# MY_beamControl_R.net
KiCad netlist of a schematic drawn in Altium Designer
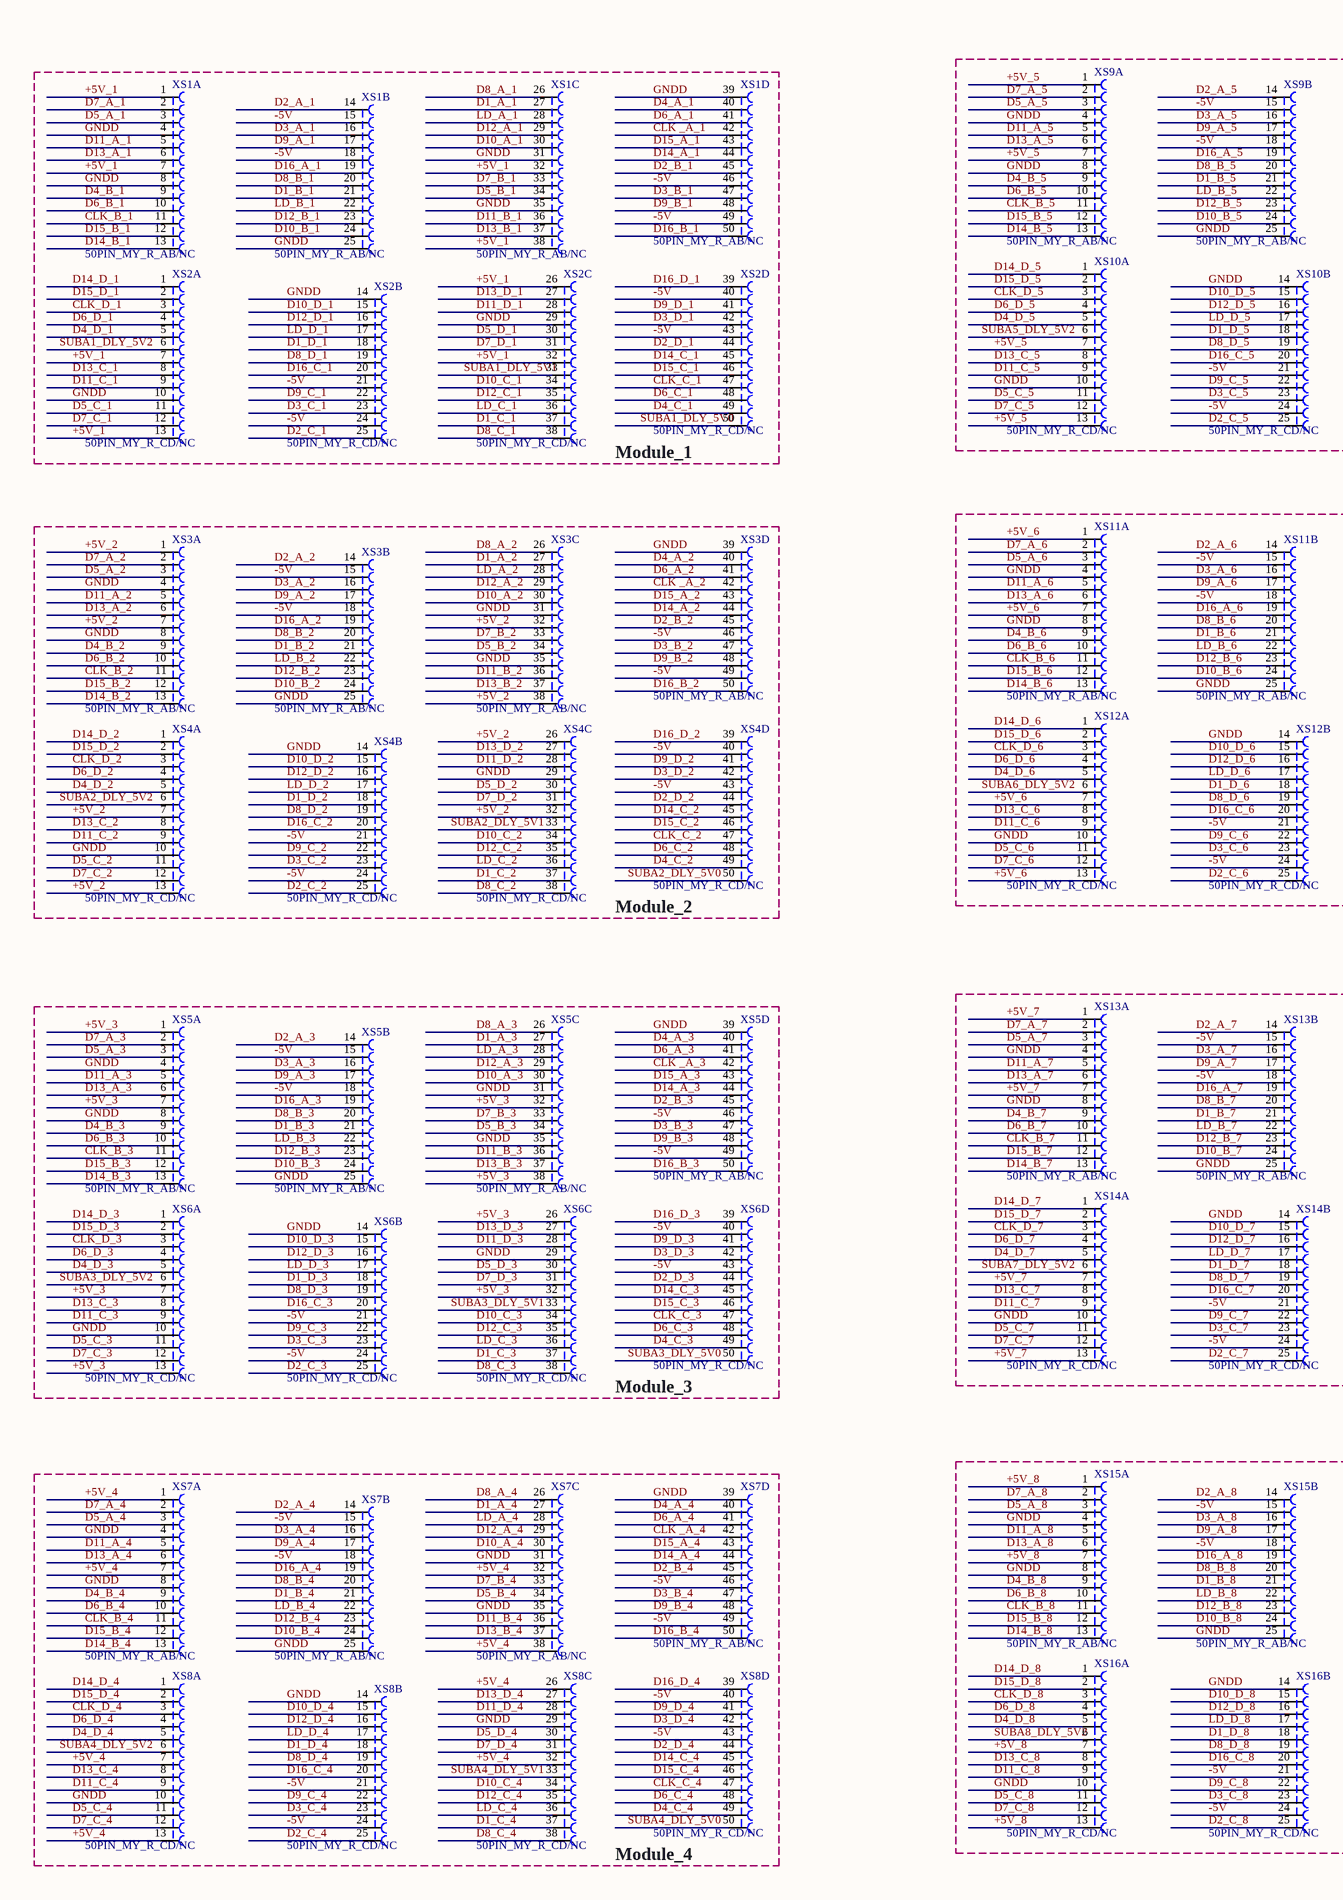
[diagram p0: MY_beamControl_R_对内接口.SchDoc, left]
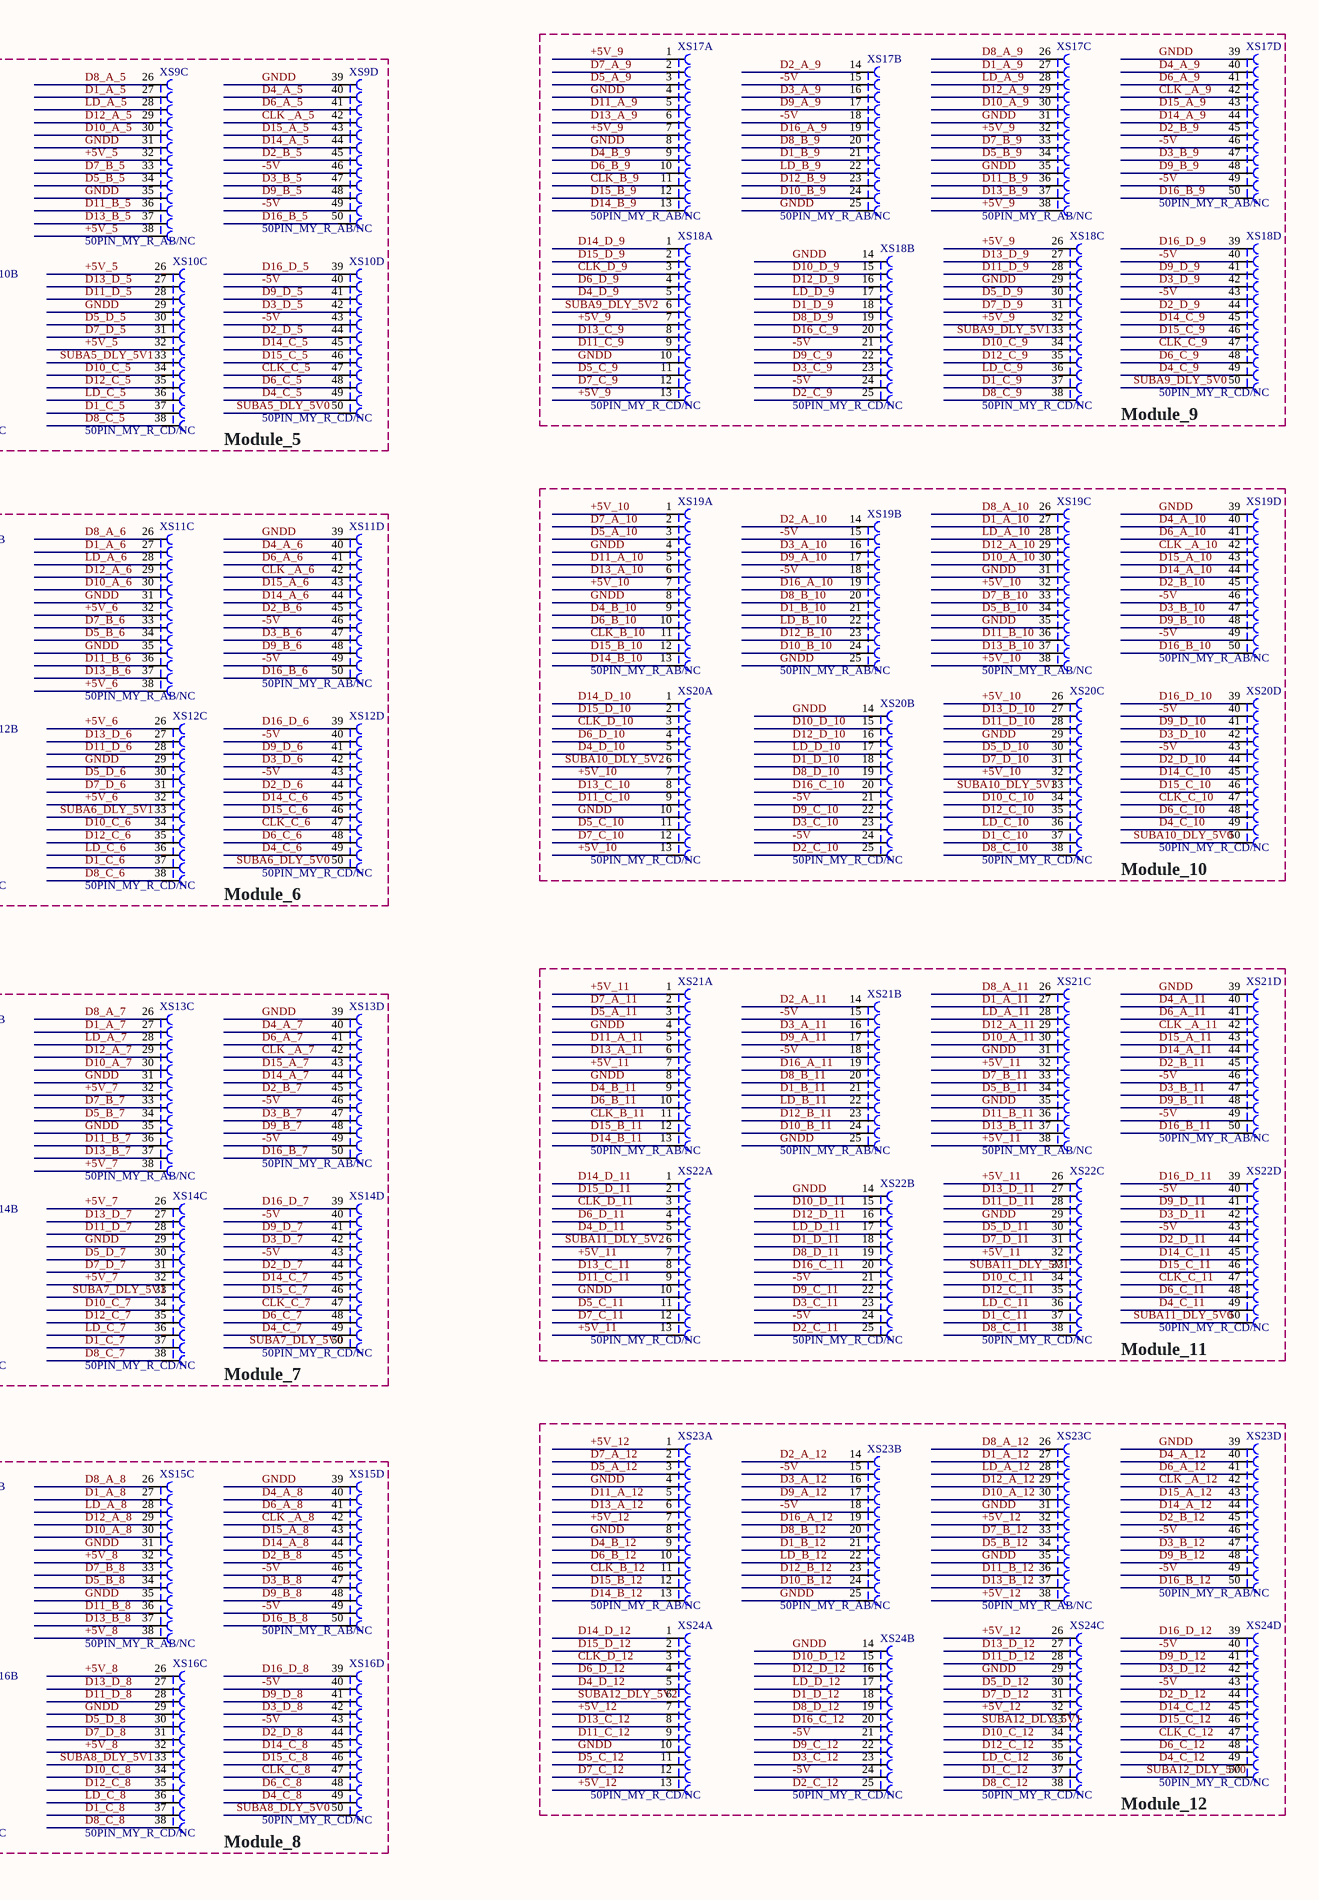
[diagram p1: MY_beamControl_R_对内接口.SchDoc, right]

(export (version "E")
  (design (tool "Eeschema 10.0.6"))
  (components
    (comp (ref "XS1")
      (value "50PIN_MY_R_AB/NC")
      (footprint "PIN50_MY")
      (libsource (lib "mySchLib") (part "50PIN_MY_R_AB"))
    )
    (comp (ref "XS2")
      (value "50PIN_MY_R_CD/NC")
      (footprint "PIN50_MY")
      (libsource (lib "mySchLib") (part "50PIN_MY_R_CD"))
    )
    (comp (ref "XS3")
      (value "50PIN_MY_R_AB/NC")
      (footprint "PIN50_MY")
      (libsource (lib "mySchLib") (part "50PIN_MY_R_AB"))
    )
    (comp (ref "XS4")
      (value "50PIN_MY_R_CD/NC")
      (footprint "PIN50_MY")
      (libsource (lib "mySchLib") (part "50PIN_MY_R_CD"))
    )
    (comp (ref "XS5")
      (value "50PIN_MY_R_AB/NC")
      (footprint "PIN50_MY")
      (libsource (lib "mySchLib") (part "50PIN_MY_R_AB"))
    )
    (comp (ref "XS6")
      (value "50PIN_MY_R_CD/NC")
      (footprint "PIN50_MY")
      (libsource (lib "mySchLib") (part "50PIN_MY_R_CD"))
    )
    (comp (ref "XS7")
      (value "50PIN_MY_R_AB/NC")
      (footprint "PIN50_MY")
      (libsource (lib "mySchLib") (part "50PIN_MY_R_AB"))
    )
    (comp (ref "XS8")
      (value "50PIN_MY_R_CD/NC")
      (footprint "PIN50_MY")
      (libsource (lib "mySchLib") (part "50PIN_MY_R_CD"))
    )
    (comp (ref "XS9")
      (value "50PIN_MY_R_AB/NC")
      (footprint "PIN50_MY")
      (libsource (lib "mySchLib") (part "50PIN_MY_R_AB"))
    )
    (comp (ref "XS10")
      (value "50PIN_MY_R_CD/NC")
      (footprint "PIN50_MY")
      (libsource (lib "mySchLib") (part "50PIN_MY_R_CD"))
    )
    (comp (ref "XS11")
      (value "50PIN_MY_R_AB/NC")
      (footprint "PIN50_MY")
      (libsource (lib "mySchLib") (part "50PIN_MY_R_AB"))
    )
    (comp (ref "XS12")
      (value "50PIN_MY_R_CD/NC")
      (footprint "PIN50_MY")
      (libsource (lib "mySchLib") (part "50PIN_MY_R_CD"))
    )
    (comp (ref "XS13")
      (value "50PIN_MY_R_AB/NC")
      (footprint "PIN50_MY")
      (libsource (lib "mySchLib") (part "50PIN_MY_R_AB"))
    )
    (comp (ref "XS14")
      (value "50PIN_MY_R_CD/NC")
      (footprint "PIN50_MY")
      (libsource (lib "mySchLib") (part "50PIN_MY_R_CD"))
    )
    (comp (ref "XS15")
      (value "50PIN_MY_R_AB/NC")
      (footprint "PIN50_MY")
      (libsource (lib "mySchLib") (part "50PIN_MY_R_AB"))
    )
    (comp (ref "XS16")
      (value "50PIN_MY_R_CD/NC")
      (footprint "PIN50_MY")
      (libsource (lib "mySchLib") (part "50PIN_MY_R_CD"))
    )
    (comp (ref "XS17")
      (value "50PIN_MY_R_AB/NC")
      (footprint "PIN50_MY")
      (libsource (lib "mySchLib") (part "50PIN_MY_R_AB"))
    )
    (comp (ref "XS18")
      (value "50PIN_MY_R_CD/NC")
      (footprint "PIN50_MY")
      (libsource (lib "mySchLib") (part "50PIN_MY_R_CD"))
    )
    (comp (ref "XS19")
      (value "50PIN_MY_R_AB/NC")
      (footprint "PIN50_MY")
      (libsource (lib "mySchLib") (part "50PIN_MY_R_AB"))
    )
    (comp (ref "XS20")
      (value "50PIN_MY_R_CD/NC")
      (footprint "PIN50_MY")
      (libsource (lib "mySchLib") (part "50PIN_MY_R_CD"))
    )
    (comp (ref "XS21")
      (value "50PIN_MY_R_AB/NC")
      (footprint "PIN50_MY")
      (libsource (lib "mySchLib") (part "50PIN_MY_R_AB"))
    )
    (comp (ref "XS22")
      (value "50PIN_MY_R_CD/NC")
      (footprint "PIN50_MY")
      (libsource (lib "mySchLib") (part "50PIN_MY_R_CD"))
    )
    (comp (ref "XS23")
      (value "50PIN_MY_R_AB/NC")
      (footprint "PIN50_MY")
      (libsource (lib "mySchLib") (part "50PIN_MY_R_AB"))
    )
    (comp (ref "XS24")
      (value "50PIN_MY_R_CD/NC")
      (footprint "PIN50_MY")
      (libsource (lib "mySchLib") (part "50PIN_MY_R_CD"))
    )
  )
  (nets
    (net (code "1") (name "/+5V_1") (class "Default")
      (node (ref "XS1") (pin "1") (pintype "passive"))
      (node (ref "XS1") (pin "32") (pintype "passive"))
      (node (ref "XS1") (pin "38") (pintype "passive"))
      (node (ref "XS1") (pin "7") (pintype "passive"))
      (node (ref "XS2") (pin "13") (pintype "passive"))
      (node (ref "XS2") (pin "26") (pintype "passive"))
      (node (ref "XS2") (pin "32") (pintype "passive"))
      (node (ref "XS2") (pin "7") (pintype "passive"))
    )
    (net (code "2") (name "/+5V_2") (class "Default")
      (node (ref "XS3") (pin "1") (pintype "passive"))
      (node (ref "XS3") (pin "32") (pintype "passive"))
      (node (ref "XS3") (pin "38") (pintype "passive"))
      (node (ref "XS3") (pin "7") (pintype "passive"))
      (node (ref "XS4") (pin "13") (pintype "passive"))
      (node (ref "XS4") (pin "26") (pintype "passive"))
      (node (ref "XS4") (pin "32") (pintype "passive"))
      (node (ref "XS4") (pin "7") (pintype "passive"))
    )
    (net (code "3") (name "/+5V_3") (class "Default")
      (node (ref "XS5") (pin "1") (pintype "passive"))
      (node (ref "XS5") (pin "32") (pintype "passive"))
      (node (ref "XS5") (pin "38") (pintype "passive"))
      (node (ref "XS5") (pin "7") (pintype "passive"))
      (node (ref "XS6") (pin "13") (pintype "passive"))
      (node (ref "XS6") (pin "26") (pintype "passive"))
      (node (ref "XS6") (pin "32") (pintype "passive"))
      (node (ref "XS6") (pin "7") (pintype "passive"))
    )
    (net (code "4") (name "/+5V_4") (class "Default")
      (node (ref "XS7") (pin "1") (pintype "passive"))
      (node (ref "XS7") (pin "32") (pintype "passive"))
      (node (ref "XS7") (pin "38") (pintype "passive"))
      (node (ref "XS7") (pin "7") (pintype "passive"))
      (node (ref "XS8") (pin "13") (pintype "passive"))
      (node (ref "XS8") (pin "26") (pintype "passive"))
      (node (ref "XS8") (pin "32") (pintype "passive"))
      (node (ref "XS8") (pin "7") (pintype "passive"))
    )
    (net (code "5") (name "/+5V_5") (class "Default")
      (node (ref "XS10") (pin "13") (pintype "passive"))
      (node (ref "XS10") (pin "26") (pintype "passive"))
      (node (ref "XS10") (pin "32") (pintype "passive"))
      (node (ref "XS10") (pin "7") (pintype "passive"))
      (node (ref "XS9") (pin "1") (pintype "passive"))
      (node (ref "XS9") (pin "32") (pintype "passive"))
      (node (ref "XS9") (pin "38") (pintype "passive"))
      (node (ref "XS9") (pin "7") (pintype "passive"))
    )
    (net (code "6") (name "/+5V_6") (class "Default")
      (node (ref "XS11") (pin "1") (pintype "passive"))
      (node (ref "XS11") (pin "32") (pintype "passive"))
      (node (ref "XS11") (pin "38") (pintype "passive"))
      (node (ref "XS11") (pin "7") (pintype "passive"))
      (node (ref "XS12") (pin "13") (pintype "passive"))
      (node (ref "XS12") (pin "26") (pintype "passive"))
      (node (ref "XS12") (pin "32") (pintype "passive"))
      (node (ref "XS12") (pin "7") (pintype "passive"))
    )
    (net (code "7") (name "/+5V_7") (class "Default")
      (node (ref "XS13") (pin "1") (pintype "passive"))
      (node (ref "XS13") (pin "32") (pintype "passive"))
      (node (ref "XS13") (pin "38") (pintype "passive"))
      (node (ref "XS13") (pin "7") (pintype "passive"))
      (node (ref "XS14") (pin "13") (pintype "passive"))
      (node (ref "XS14") (pin "26") (pintype "passive"))
      (node (ref "XS14") (pin "32") (pintype "passive"))
      (node (ref "XS14") (pin "7") (pintype "passive"))
    )
    (net (code "8") (name "/+5V_8") (class "Default")
      (node (ref "XS15") (pin "1") (pintype "passive"))
      (node (ref "XS15") (pin "32") (pintype "passive"))
      (node (ref "XS15") (pin "38") (pintype "passive"))
      (node (ref "XS15") (pin "7") (pintype "passive"))
      (node (ref "XS16") (pin "13") (pintype "passive"))
      (node (ref "XS16") (pin "26") (pintype "passive"))
      (node (ref "XS16") (pin "32") (pintype "passive"))
      (node (ref "XS16") (pin "7") (pintype "passive"))
    )
    (net (code "9") (name "/+5V_9") (class "Default")
      (node (ref "XS17") (pin "1") (pintype "passive"))
      (node (ref "XS17") (pin "32") (pintype "passive"))
      (node (ref "XS17") (pin "38") (pintype "passive"))
      (node (ref "XS17") (pin "7") (pintype "passive"))
      (node (ref "XS18") (pin "13") (pintype "passive"))
      (node (ref "XS18") (pin "26") (pintype "passive"))
      (node (ref "XS18") (pin "32") (pintype "passive"))
      (node (ref "XS18") (pin "7") (pintype "passive"))
    )
    (net (code "10") (name "/+5V_10") (class "Default")
      (node (ref "XS19") (pin "1") (pintype "passive"))
      (node (ref "XS19") (pin "32") (pintype "passive"))
      (node (ref "XS19") (pin "38") (pintype "passive"))
      (node (ref "XS19") (pin "7") (pintype "passive"))
      (node (ref "XS20") (pin "13") (pintype "passive"))
      (node (ref "XS20") (pin "26") (pintype "passive"))
      (node (ref "XS20") (pin "32") (pintype "passive"))
      (node (ref "XS20") (pin "7") (pintype "passive"))
    )
    (net (code "11") (name "/+5V_11") (class "Default")
      (node (ref "XS21") (pin "1") (pintype "passive"))
      (node (ref "XS21") (pin "32") (pintype "passive"))
      (node (ref "XS21") (pin "38") (pintype "passive"))
      (node (ref "XS21") (pin "7") (pintype "passive"))
      (node (ref "XS22") (pin "13") (pintype "passive"))
      (node (ref "XS22") (pin "26") (pintype "passive"))
      (node (ref "XS22") (pin "32") (pintype "passive"))
      (node (ref "XS22") (pin "7") (pintype "passive"))
    )
    (net (code "12") (name "/+5V_12") (class "Default")
      (node (ref "XS23") (pin "1") (pintype "passive"))
      (node (ref "XS23") (pin "32") (pintype "passive"))
      (node (ref "XS23") (pin "38") (pintype "passive"))
      (node (ref "XS23") (pin "7") (pintype "passive"))
      (node (ref "XS24") (pin "13") (pintype "passive"))
      (node (ref "XS24") (pin "26") (pintype "passive"))
      (node (ref "XS24") (pin "32") (pintype "passive"))
      (node (ref "XS24") (pin "7") (pintype "passive"))
    )
    (net (code "13") (name "/-5V") (class "Default")
      (node (ref "XS1") (pin "15") (pintype "passive"))
      (node (ref "XS1") (pin "18") (pintype "passive"))
      (node (ref "XS1") (pin "46") (pintype "passive"))
      (node (ref "XS1") (pin "49") (pintype "passive"))
      (node (ref "XS10") (pin "21") (pintype "passive"))
      (node (ref "XS10") (pin "24") (pintype "passive"))
      (node (ref "XS10") (pin "40") (pintype "passive"))
      (node (ref "XS10") (pin "43") (pintype "passive"))
      (node (ref "XS11") (pin "15") (pintype "passive"))
      (node (ref "XS11") (pin "18") (pintype "passive"))
      (node (ref "XS11") (pin "46") (pintype "passive"))
      (node (ref "XS11") (pin "49") (pintype "passive"))
      (node (ref "XS12") (pin "21") (pintype "passive"))
      (node (ref "XS12") (pin "24") (pintype "passive"))
      (node (ref "XS12") (pin "40") (pintype "passive"))
      (node (ref "XS12") (pin "43") (pintype "passive"))
      (node (ref "XS13") (pin "15") (pintype "passive"))
      (node (ref "XS13") (pin "18") (pintype "passive"))
      (node (ref "XS13") (pin "46") (pintype "passive"))
      (node (ref "XS13") (pin "49") (pintype "passive"))
      (node (ref "XS14") (pin "21") (pintype "passive"))
      (node (ref "XS14") (pin "24") (pintype "passive"))
      (node (ref "XS14") (pin "40") (pintype "passive"))
      (node (ref "XS14") (pin "43") (pintype "passive"))
      (node (ref "XS15") (pin "15") (pintype "passive"))
      (node (ref "XS15") (pin "18") (pintype "passive"))
      (node (ref "XS15") (pin "46") (pintype "passive"))
      (node (ref "XS15") (pin "49") (pintype "passive"))
      (node (ref "XS16") (pin "21") (pintype "passive"))
      (node (ref "XS16") (pin "24") (pintype "passive"))
      (node (ref "XS16") (pin "40") (pintype "passive"))
      (node (ref "XS16") (pin "43") (pintype "passive"))
      (node (ref "XS17") (pin "15") (pintype "passive"))
      (node (ref "XS17") (pin "18") (pintype "passive"))
      (node (ref "XS17") (pin "46") (pintype "passive"))
      (node (ref "XS17") (pin "49") (pintype "passive"))
      (node (ref "XS18") (pin "21") (pintype "passive"))
      (node (ref "XS18") (pin "24") (pintype "passive"))
      (node (ref "XS18") (pin "40") (pintype "passive"))
      (node (ref "XS18") (pin "43") (pintype "passive"))
      (node (ref "XS19") (pin "15") (pintype "passive"))
      (node (ref "XS19") (pin "18") (pintype "passive"))
      (node (ref "XS19") (pin "46") (pintype "passive"))
      (node (ref "XS19") (pin "49") (pintype "passive"))
      (node (ref "XS2") (pin "21") (pintype "passive"))
      (node (ref "XS2") (pin "24") (pintype "passive"))
      (node (ref "XS2") (pin "40") (pintype "passive"))
      (node (ref "XS2") (pin "43") (pintype "passive"))
      (node (ref "XS20") (pin "21") (pintype "passive"))
      (node (ref "XS20") (pin "24") (pintype "passive"))
      (node (ref "XS20") (pin "40") (pintype "passive"))
      (node (ref "XS20") (pin "43") (pintype "passive"))
      (node (ref "XS21") (pin "15") (pintype "passive"))
      (node (ref "XS21") (pin "18") (pintype "passive"))
      (node (ref "XS21") (pin "46") (pintype "passive"))
      (node (ref "XS21") (pin "49") (pintype "passive"))
      (node (ref "XS22") (pin "21") (pintype "passive"))
      (node (ref "XS22") (pin "24") (pintype "passive"))
      (node (ref "XS22") (pin "40") (pintype "passive"))
      (node (ref "XS22") (pin "43") (pintype "passive"))
      (node (ref "XS23") (pin "15") (pintype "passive"))
      (node (ref "XS23") (pin "18") (pintype "passive"))
      (node (ref "XS23") (pin "46") (pintype "passive"))
      (node (ref "XS23") (pin "49") (pintype "passive"))
      (node (ref "XS24") (pin "21") (pintype "passive"))
      (node (ref "XS24") (pin "24") (pintype "passive"))
      (node (ref "XS24") (pin "40") (pintype "passive"))
      (node (ref "XS24") (pin "43") (pintype "passive"))
      (node (ref "XS3") (pin "15") (pintype "passive"))
      (node (ref "XS3") (pin "18") (pintype "passive"))
      (node (ref "XS3") (pin "46") (pintype "passive"))
      (node (ref "XS3") (pin "49") (pintype "passive"))
      (node (ref "XS4") (pin "21") (pintype "passive"))
      (node (ref "XS4") (pin "24") (pintype "passive"))
      (node (ref "XS4") (pin "40") (pintype "passive"))
      (node (ref "XS4") (pin "43") (pintype "passive"))
      (node (ref "XS5") (pin "15") (pintype "passive"))
      (node (ref "XS5") (pin "18") (pintype "passive"))
      (node (ref "XS5") (pin "46") (pintype "passive"))
      (node (ref "XS5") (pin "49") (pintype "passive"))
      (node (ref "XS6") (pin "21") (pintype "passive"))
      (node (ref "XS6") (pin "24") (pintype "passive"))
      (node (ref "XS6") (pin "40") (pintype "passive"))
      (node (ref "XS6") (pin "43") (pintype "passive"))
      (node (ref "XS7") (pin "15") (pintype "passive"))
      (node (ref "XS7") (pin "18") (pintype "passive"))
      (node (ref "XS7") (pin "46") (pintype "passive"))
      (node (ref "XS7") (pin "49") (pintype "passive"))
      (node (ref "XS8") (pin "21") (pintype "passive"))
      (node (ref "XS8") (pin "24") (pintype "passive"))
      (node (ref "XS8") (pin "40") (pintype "passive"))
      (node (ref "XS8") (pin "43") (pintype "passive"))
      (node (ref "XS9") (pin "15") (pintype "passive"))
      (node (ref "XS9") (pin "18") (pintype "passive"))
      (node (ref "XS9") (pin "46") (pintype "passive"))
      (node (ref "XS9") (pin "49") (pintype "passive"))
    )
    (net (code "14") (name "/CLK _A_1") (class "Default") (node (ref "XS1") (pin "42") (pintype "passive")))
    (net (code "15") (name "/CLK _A_2") (class "Default") (node (ref "XS3") (pin "42") (pintype "passive")))
    (net (code "16") (name "/CLK _A_3") (class "Default") (node (ref "XS5") (pin "42") (pintype "passive")))
    (net (code "17") (name "/CLK _A_4") (class "Default") (node (ref "XS7") (pin "42") (pintype "passive")))
    (net (code "18") (name "/CLK _A_5") (class "Default") (node (ref "XS9") (pin "42") (pintype "passive")))
    (net (code "19") (name "/CLK _A_6") (class "Default") (node (ref "XS11") (pin "42") (pintype "passive")))
    (net (code "20") (name "/CLK _A_7") (class "Default") (node (ref "XS13") (pin "42") (pintype "passive")))
    (net (code "21") (name "/CLK _A_8") (class "Default") (node (ref "XS15") (pin "42") (pintype "passive")))
    (net (code "22") (name "/CLK _A_9") (class "Default") (node (ref "XS17") (pin "42") (pintype "passive")))
    (net (code "23") (name "/CLK _A_10") (class "Default") (node (ref "XS19") (pin "42") (pintype "passive")))
    (net (code "24") (name "/CLK _A_11") (class "Default") (node (ref "XS21") (pin "42") (pintype "passive")))
    (net (code "25") (name "/CLK _A_12") (class "Default") (node (ref "XS23") (pin "42") (pintype "passive")))
    (net (code "26") (name "/CLK_B_1") (class "Default") (node (ref "XS1") (pin "11") (pintype "passive")))
    (net (code "27") (name "/CLK_B_2") (class "Default") (node (ref "XS3") (pin "11") (pintype "passive")))
    (net (code "28") (name "/CLK_B_3") (class "Default") (node (ref "XS5") (pin "11") (pintype "passive")))
    (net (code "29") (name "/CLK_B_4") (class "Default") (node (ref "XS7") (pin "11") (pintype "passive")))
    (net (code "30") (name "/CLK_B_5") (class "Default") (node (ref "XS9") (pin "11") (pintype "passive")))
    (net (code "31") (name "/CLK_B_6") (class "Default") (node (ref "XS11") (pin "11") (pintype "passive")))
    (net (code "32") (name "/CLK_B_7") (class "Default") (node (ref "XS13") (pin "11") (pintype "passive")))
    (net (code "33") (name "/CLK_B_8") (class "Default") (node (ref "XS15") (pin "11") (pintype "passive")))
    (net (code "34") (name "/CLK_B_9") (class "Default") (node (ref "XS17") (pin "11") (pintype "passive")))
    (net (code "35") (name "/CLK_B_10") (class "Default") (node (ref "XS19") (pin "11") (pintype "passive")))
    (net (code "36") (name "/CLK_B_11") (class "Default") (node (ref "XS21") (pin "11") (pintype "passive")))
    (net (code "37") (name "/CLK_B_12") (class "Default") (node (ref "XS23") (pin "11") (pintype "passive")))
    (net (code "38") (name "/CLK_C_1") (class "Default") (node (ref "XS2") (pin "47") (pintype "passive")))
    (net (code "39") (name "/CLK_C_2") (class "Default") (node (ref "XS4") (pin "47") (pintype "passive")))
    (net (code "40") (name "/CLK_C_3") (class "Default") (node (ref "XS6") (pin "47") (pintype "passive")))
    (net (code "41") (name "/CLK_C_4") (class "Default") (node (ref "XS8") (pin "47") (pintype "passive")))
    (net (code "42") (name "/CLK_C_5") (class "Default") (node (ref "XS10") (pin "47") (pintype "passive")))
    (net (code "43") (name "/CLK_C_6") (class "Default") (node (ref "XS12") (pin "47") (pintype "passive")))
    (net (code "44") (name "/CLK_C_7") (class "Default") (node (ref "XS14") (pin "47") (pintype "passive")))
    (net (code "45") (name "/CLK_C_8") (class "Default") (node (ref "XS16") (pin "47") (pintype "passive")))
    (net (code "46") (name "/CLK_C_9") (class "Default") (node (ref "XS18") (pin "47") (pintype "passive")))
    (net (code "47") (name "/CLK_C_10") (class "Default") (node (ref "XS20") (pin "47") (pintype "passive")))
    (net (code "48") (name "/CLK_C_11") (class "Default") (node (ref "XS22") (pin "47") (pintype "passive")))
    (net (code "49") (name "/CLK_C_12") (class "Default") (node (ref "XS24") (pin "47") (pintype "passive")))
    (net (code "50") (name "/CLK_D_1") (class "Default") (node (ref "XS2") (pin "3") (pintype "passive")))
    (net (code "51") (name "/CLK_D_2") (class "Default") (node (ref "XS4") (pin "3") (pintype "passive")))
    (net (code "52") (name "/CLK_D_3") (class "Default") (node (ref "XS6") (pin "3") (pintype "passive")))
    (net (code "53") (name "/CLK_D_4") (class "Default") (node (ref "XS8") (pin "3") (pintype "passive")))
    (net (code "54") (name "/CLK_D_5") (class "Default") (node (ref "XS10") (pin "3") (pintype "passive")))
    (net (code "55") (name "/CLK_D_6") (class "Default") (node (ref "XS12") (pin "3") (pintype "passive")))
    (net (code "56") (name "/CLK_D_7") (class "Default") (node (ref "XS14") (pin "3") (pintype "passive")))
    (net (code "57") (name "/CLK_D_8") (class "Default") (node (ref "XS16") (pin "3") (pintype "passive")))
    (net (code "58") (name "/CLK_D_9") (class "Default") (node (ref "XS18") (pin "3") (pintype "passive")))
    (net (code "59") (name "/CLK_D_10") (class "Default") (node (ref "XS20") (pin "3") (pintype "passive")))
    (net (code "60") (name "/CLK_D_11") (class "Default") (node (ref "XS22") (pin "3") (pintype "passive")))
    (net (code "61") (name "/CLK_D_12") (class "Default") (node (ref "XS24") (pin "3") (pintype "passive")))
    (net (code "62") (name "/D1_A_1") (class "Default") (node (ref "XS1") (pin "27") (pintype "passive")))
    (net (code "63") (name "/D1_A_2") (class "Default") (node (ref "XS3") (pin "27") (pintype "passive")))
    (net (code "64") (name "/D1_A_3") (class "Default") (node (ref "XS5") (pin "27") (pintype "passive")))
    (net (code "65") (name "/D1_A_4") (class "Default") (node (ref "XS7") (pin "27") (pintype "passive")))
    (net (code "66") (name "/D1_A_5") (class "Default") (node (ref "XS9") (pin "27") (pintype "passive")))
    (net (code "67") (name "/D1_A_6") (class "Default") (node (ref "XS11") (pin "27") (pintype "passive")))
    (net (code "68") (name "/D1_A_7") (class "Default") (node (ref "XS13") (pin "27") (pintype "passive")))
    (net (code "69") (name "/D1_A_8") (class "Default") (node (ref "XS15") (pin "27") (pintype "passive")))
    (net (code "70") (name "/D1_A_9") (class "Default") (node (ref "XS17") (pin "27") (pintype "passive")))
    (net (code "71") (name "/D1_A_10") (class "Default") (node (ref "XS19") (pin "27") (pintype "passive")))
    (net (code "72") (name "/D1_A_11") (class "Default") (node (ref "XS21") (pin "27") (pintype "passive")))
    (net (code "73") (name "/D1_A_12") (class "Default") (node (ref "XS23") (pin "27") (pintype "passive")))
    (net (code "74") (name "/D1_B_1") (class "Default") (node (ref "XS1") (pin "21") (pintype "passive")))
    (net (code "75") (name "/D1_B_2") (class "Default") (node (ref "XS3") (pin "21") (pintype "passive")))
    (net (code "76") (name "/D1_B_3") (class "Default") (node (ref "XS5") (pin "21") (pintype "passive")))
    (net (code "77") (name "/D1_B_4") (class "Default") (node (ref "XS7") (pin "21") (pintype "passive")))
    (net (code "78") (name "/D1_B_5") (class "Default") (node (ref "XS9") (pin "21") (pintype "passive")))
    (net (code "79") (name "/D1_B_6") (class "Default") (node (ref "XS11") (pin "21") (pintype "passive")))
    (net (code "80") (name "/D1_B_7") (class "Default") (node (ref "XS13") (pin "21") (pintype "passive")))
    (net (code "81") (name "/D1_B_8") (class "Default") (node (ref "XS15") (pin "21") (pintype "passive")))
    (net (code "82") (name "/D1_B_9") (class "Default") (node (ref "XS17") (pin "21") (pintype "passive")))
    (net (code "83") (name "/D1_B_10") (class "Default") (node (ref "XS19") (pin "21") (pintype "passive")))
    (net (code "84") (name "/D1_B_11") (class "Default") (node (ref "XS21") (pin "21") (pintype "passive")))
    (net (code "85") (name "/D1_B_12") (class "Default") (node (ref "XS23") (pin "21") (pintype "passive")))
    (net (code "86") (name "/D1_C_1") (class "Default") (node (ref "XS2") (pin "37") (pintype "passive")))
    (net (code "87") (name "/D1_C_2") (class "Default") (node (ref "XS4") (pin "37") (pintype "passive")))
    (net (code "88") (name "/D1_C_3") (class "Default") (node (ref "XS6") (pin "37") (pintype "passive")))
    (net (code "89") (name "/D1_C_4") (class "Default") (node (ref "XS8") (pin "37") (pintype "passive")))
    (net (code "90") (name "/D1_C_5") (class "Default") (node (ref "XS10") (pin "37") (pintype "passive")))
    (net (code "91") (name "/D1_C_6") (class "Default") (node (ref "XS12") (pin "37") (pintype "passive")))
    (net (code "92") (name "/D1_C_7") (class "Default") (node (ref "XS14") (pin "37") (pintype "passive")))
    (net (code "93") (name "/D1_C_8") (class "Default") (node (ref "XS16") (pin "37") (pintype "passive")))
    (net (code "94") (name "/D1_C_9") (class "Default") (node (ref "XS18") (pin "37") (pintype "passive")))
    (net (code "95") (name "/D1_C_10") (class "Default") (node (ref "XS20") (pin "37") (pintype "passive")))
    (net (code "96") (name "/D1_C_11") (class "Default") (node (ref "XS22") (pin "37") (pintype "passive")))
    (net (code "97") (name "/D1_C_12") (class "Default") (node (ref "XS24") (pin "37") (pintype "passive")))
    (net (code "98") (name "/D1_D_1") (class "Default") (node (ref "XS2") (pin "18") (pintype "passive")))
    (net (code "99") (name "/D1_D_2") (class "Default") (node (ref "XS4") (pin "18") (pintype "passive")))
    (net (code "100") (name "/D1_D_3") (class "Default") (node (ref "XS6") (pin "18") (pintype "passive")))
    (net (code "101") (name "/D1_D_4") (class "Default") (node (ref "XS8") (pin "18") (pintype "passive")))
    (net (code "102") (name "/D1_D_5") (class "Default") (node (ref "XS10") (pin "18") (pintype "passive")))
    (net (code "103") (name "/D1_D_6") (class "Default") (node (ref "XS12") (pin "18") (pintype "passive")))
    (net (code "104") (name "/D1_D_7") (class "Default") (node (ref "XS14") (pin "18") (pintype "passive")))
    (net (code "105") (name "/D1_D_8") (class "Default") (node (ref "XS16") (pin "18") (pintype "passive")))
    (net (code "106") (name "/D1_D_9") (class "Default") (node (ref "XS18") (pin "18") (pintype "passive")))
    (net (code "107") (name "/D1_D_10") (class "Default") (node (ref "XS20") (pin "18") (pintype "passive")))
    (net (code "108") (name "/D1_D_11") (class "Default") (node (ref "XS22") (pin "18") (pintype "passive")))
    (net (code "109") (name "/D1_D_12") (class "Default") (node (ref "XS24") (pin "18") (pintype "passive")))
    (net (code "110") (name "/D2_A_1") (class "Default") (node (ref "XS1") (pin "14") (pintype "passive")))
    (net (code "111") (name "/D2_A_2") (class "Default") (node (ref "XS3") (pin "14") (pintype "passive")))
    (net (code "112") (name "/D2_A_3") (class "Default") (node (ref "XS5") (pin "14") (pintype "passive")))
    (net (code "113") (name "/D2_A_4") (class "Default") (node (ref "XS7") (pin "14") (pintype "passive")))
    (net (code "114") (name "/D2_A_5") (class "Default") (node (ref "XS9") (pin "14") (pintype "passive")))
    (net (code "115") (name "/D2_A_6") (class "Default") (node (ref "XS11") (pin "14") (pintype "passive")))
    (net (code "116") (name "/D2_A_7") (class "Default") (node (ref "XS13") (pin "14") (pintype "passive")))
    (net (code "117") (name "/D2_A_8") (class "Default") (node (ref "XS15") (pin "14") (pintype "passive")))
    (net (code "118") (name "/D2_A_9") (class "Default") (node (ref "XS17") (pin "14") (pintype "passive")))
    (net (code "119") (name "/D2_A_10") (class "Default") (node (ref "XS19") (pin "14") (pintype "passive")))
    (net (code "120") (name "/D2_A_11") (class "Default") (node (ref "XS21") (pin "14") (pintype "passive")))
    (net (code "121") (name "/D2_A_12") (class "Default") (node (ref "XS23") (pin "14") (pintype "passive")))
    (net (code "122") (name "/D2_B_1") (class "Default") (node (ref "XS1") (pin "45") (pintype "passive")))
    (net (code "123") (name "/D2_B_2") (class "Default") (node (ref "XS3") (pin "45") (pintype "passive")))
    (net (code "124") (name "/D2_B_3") (class "Default") (node (ref "XS5") (pin "45") (pintype "passive")))
    (net (code "125") (name "/D2_B_4") (class "Default") (node (ref "XS7") (pin "45") (pintype "passive")))
    (net (code "126") (name "/D2_B_5") (class "Default") (node (ref "XS9") (pin "45") (pintype "passive")))
    (net (code "127") (name "/D2_B_6") (class "Default") (node (ref "XS11") (pin "45") (pintype "passive")))
    (net (code "128") (name "/D2_B_7") (class "Default") (node (ref "XS13") (pin "45") (pintype "passive")))
    (net (code "129") (name "/D2_B_8") (class "Default") (node (ref "XS15") (pin "45") (pintype "passive")))
    (net (code "130") (name "/D2_B_9") (class "Default") (node (ref "XS17") (pin "45") (pintype "passive")))
    (net (code "131") (name "/D2_B_10") (class "Default") (node (ref "XS19") (pin "45") (pintype "passive")))
    (net (code "132") (name "/D2_B_11") (class "Default") (node (ref "XS21") (pin "45") (pintype "passive")))
    (net (code "133") (name "/D2_B_12") (class "Default") (node (ref "XS23") (pin "45") (pintype "passive")))
    (net (code "134") (name "/D2_C_1") (class "Default") (node (ref "XS2") (pin "25") (pintype "passive")))
    (net (code "135") (name "/D2_C_2") (class "Default") (node (ref "XS4") (pin "25") (pintype "passive")))
    (net (code "136") (name "/D2_C_3") (class "Default") (node (ref "XS6") (pin "25") (pintype "passive")))
    (net (code "137") (name "/D2_C_4") (class "Default") (node (ref "XS8") (pin "25") (pintype "passive")))
    (net (code "138") (name "/D2_C_5") (class "Default") (node (ref "XS10") (pin "25") (pintype "passive")))
    (net (code "139") (name "/D2_C_6") (class "Default") (node (ref "XS12") (pin "25") (pintype "passive")))
    (net (code "140") (name "/D2_C_7") (class "Default") (node (ref "XS14") (pin "25") (pintype "passive")))
    (net (code "141") (name "/D2_C_8") (class "Default") (node (ref "XS16") (pin "25") (pintype "passive")))
    (net (code "142") (name "/D2_C_9") (class "Default") (node (ref "XS18") (pin "25") (pintype "passive")))
    (net (code "143") (name "/D2_C_10") (class "Default") (node (ref "XS20") (pin "25") (pintype "passive")))
    (net (code "144") (name "/D2_C_11") (class "Default") (node (ref "XS22") (pin "25") (pintype "passive")))
    (net (code "145") (name "/D2_C_12") (class "Default") (node (ref "XS24") (pin "25") (pintype "passive")))
    (net (code "146") (name "/D2_D_1") (class "Default") (node (ref "XS2") (pin "44") (pintype "passive")))
    (net (code "147") (name "/D2_D_2") (class "Default") (node (ref "XS4") (pin "44") (pintype "passive")))
    (net (code "148") (name "/D2_D_3") (class "Default") (node (ref "XS6") (pin "44") (pintype "passive")))
    (net (code "149") (name "/D2_D_4") (class "Default") (node (ref "XS8") (pin "44") (pintype "passive")))
    (net (code "150") (name "/D2_D_5") (class "Default") (node (ref "XS10") (pin "44") (pintype "passive")))
    (net (code "151") (name "/D2_D_6") (class "Default") (node (ref "XS12") (pin "44") (pintype "passive")))
    (net (code "152") (name "/D2_D_7") (class "Default") (node (ref "XS14") (pin "44") (pintype "passive")))
    (net (code "153") (name "/D2_D_8") (class "Default") (node (ref "XS16") (pin "44") (pintype "passive")))
    (net (code "154") (name "/D2_D_9") (class "Default") (node (ref "XS18") (pin "44") (pintype "passive")))
    (net (code "155") (name "/D2_D_10") (class "Default") (node (ref "XS20") (pin "44") (pintype "passive")))
    (net (code "156") (name "/D2_D_11") (class "Default") (node (ref "XS22") (pin "44") (pintype "passive")))
    (net (code "157") (name "/D2_D_12") (class "Default") (node (ref "XS24") (pin "44") (pintype "passive")))
    (net (code "158") (name "/D3_A_1") (class "Default") (node (ref "XS1") (pin "16") (pintype "passive")))
    (net (code "159") (name "/D3_A_2") (class "Default") (node (ref "XS3") (pin "16") (pintype "passive")))
    (net (code "160") (name "/D3_A_3") (class "Default") (node (ref "XS5") (pin "16") (pintype "passive")))
    (net (code "161") (name "/D3_A_4") (class "Default") (node (ref "XS7") (pin "16") (pintype "passive")))
    (net (code "162") (name "/D3_A_5") (class "Default") (node (ref "XS9") (pin "16") (pintype "passive")))
    (net (code "163") (name "/D3_A_6") (class "Default") (node (ref "XS11") (pin "16") (pintype "passive")))
    (net (code "164") (name "/D3_A_7") (class "Default") (node (ref "XS13") (pin "16") (pintype "passive")))
    (net (code "165") (name "/D3_A_8") (class "Default") (node (ref "XS15") (pin "16") (pintype "passive")))
    (net (code "166") (name "/D3_A_9") (class "Default") (node (ref "XS17") (pin "16") (pintype "passive")))
    (net (code "167") (name "/D3_A_10") (class "Default") (node (ref "XS19") (pin "16") (pintype "passive")))
    (net (code "168") (name "/D3_A_11") (class "Default") (node (ref "XS21") (pin "16") (pintype "passive")))
    (net (code "169") (name "/D3_A_12") (class "Default") (node (ref "XS23") (pin "16") (pintype "passive")))
    (net (code "170") (name "/D3_B_1") (class "Default") (node (ref "XS1") (pin "47") (pintype "passive")))
    (net (code "171") (name "/D3_B_2") (class "Default") (node (ref "XS3") (pin "47") (pintype "passive")))
    (net (code "172") (name "/D3_B_3") (class "Default") (node (ref "XS5") (pin "47") (pintype "passive")))
    (net (code "173") (name "/D3_B_4") (class "Default") (node (ref "XS7") (pin "47") (pintype "passive")))
    (net (code "174") (name "/D3_B_5") (class "Default") (node (ref "XS9") (pin "47") (pintype "passive")))
    (net (code "175") (name "/D3_B_6") (class "Default") (node (ref "XS11") (pin "47") (pintype "passive")))
    (net (code "176") (name "/D3_B_7") (class "Default") (node (ref "XS13") (pin "47") (pintype "passive")))
    (net (code "177") (name "/D3_B_8") (class "Default") (node (ref "XS15") (pin "47") (pintype "passive")))
    (net (code "178") (name "/D3_B_9") (class "Default") (node (ref "XS17") (pin "47") (pintype "passive")))
    (net (code "179") (name "/D3_B_10") (class "Default") (node (ref "XS19") (pin "47") (pintype "passive")))
    (net (code "180") (name "/D3_B_11") (class "Default") (node (ref "XS21") (pin "47") (pintype "passive")))
    (net (code "181") (name "/D3_B_12") (class "Default") (node (ref "XS23") (pin "47") (pintype "passive")))
    (net (code "182") (name "/D3_C_1") (class "Default") (node (ref "XS2") (pin "23") (pintype "passive")))
    (net (code "183") (name "/D3_C_2") (class "Default") (node (ref "XS4") (pin "23") (pintype "passive")))
    (net (code "184") (name "/D3_C_3") (class "Default") (node (ref "XS6") (pin "23") (pintype "passive")))
    (net (code "185") (name "/D3_C_4") (class "Default") (node (ref "XS8") (pin "23") (pintype "passive")))
    (net (code "186") (name "/D3_C_5") (class "Default") (node (ref "XS10") (pin "23") (pintype "passive")))
    (net (code "187") (name "/D3_C_6") (class "Default") (node (ref "XS12") (pin "23") (pintype "passive")))
    (net (code "188") (name "/D3_C_7") (class "Default") (node (ref "XS14") (pin "23") (pintype "passive")))
    (net (code "189") (name "/D3_C_8") (class "Default") (node (ref "XS16") (pin "23") (pintype "passive")))
    (net (code "190") (name "/D3_C_9") (class "Default") (node (ref "XS18") (pin "23") (pintype "passive")))
    (net (code "191") (name "/D3_C_10") (class "Default") (node (ref "XS20") (pin "23") (pintype "passive")))
    (net (code "192") (name "/D3_C_11") (class "Default") (node (ref "XS22") (pin "23") (pintype "passive")))
    (net (code "193") (name "/D3_C_12") (class "Default") (node (ref "XS24") (pin "23") (pintype "passive")))
    (net (code "194") (name "/D3_D_1") (class "Default") (node (ref "XS2") (pin "42") (pintype "passive")))
    (net (code "195") (name "/D3_D_2") (class "Default") (node (ref "XS4") (pin "42") (pintype "passive")))
    (net (code "196") (name "/D3_D_3") (class "Default") (node (ref "XS6") (pin "42") (pintype "passive")))
    (net (code "197") (name "/D3_D_4") (class "Default") (node (ref "XS8") (pin "42") (pintype "passive")))
    (net (code "198") (name "/D3_D_5") (class "Default") (node (ref "XS10") (pin "42") (pintype "passive")))
    (net (code "199") (name "/D3_D_6") (class "Default") (node (ref "XS12") (pin "42") (pintype "passive")))
    (net (code "200") (name "/D3_D_7") (class "Default") (node (ref "XS14") (pin "42") (pintype "passive")))
    (net (code "201") (name "/D3_D_8") (class "Default") (node (ref "XS16") (pin "42") (pintype "passive")))
    (net (code "202") (name "/D3_D_9") (class "Default") (node (ref "XS18") (pin "42") (pintype "passive")))
    (net (code "203") (name "/D3_D_10") (class "Default") (node (ref "XS20") (pin "42") (pintype "passive")))
    (net (code "204") (name "/D3_D_11") (class "Default") (node (ref "XS22") (pin "42") (pintype "passive")))
    (net (code "205") (name "/D3_D_12") (class "Default") (node (ref "XS24") (pin "42") (pintype "passive")))
    (net (code "206") (name "/D4_A_1") (class "Default") (node (ref "XS1") (pin "40") (pintype "passive")))
    (net (code "207") (name "/D4_A_2") (class "Default") (node (ref "XS3") (pin "40") (pintype "passive")))
    (net (code "208") (name "/D4_A_3") (class "Default") (node (ref "XS5") (pin "40") (pintype "passive")))
    (net (code "209") (name "/D4_A_4") (class "Default") (node (ref "XS7") (pin "40") (pintype "passive")))
    (net (code "210") (name "/D4_A_5") (class "Default") (node (ref "XS9") (pin "40") (pintype "passive")))
    (net (code "211") (name "/D4_A_6") (class "Default") (node (ref "XS11") (pin "40") (pintype "passive")))
    (net (code "212") (name "/D4_A_7") (class "Default") (node (ref "XS13") (pin "40") (pintype "passive")))
    (net (code "213") (name "/D4_A_8") (class "Default") (node (ref "XS15") (pin "40") (pintype "passive")))
    (net (code "214") (name "/D4_A_9") (class "Default") (node (ref "XS17") (pin "40") (pintype "passive")))
    (net (code "215") (name "/D4_A_10") (class "Default") (node (ref "XS19") (pin "40") (pintype "passive")))
    (net (code "216") (name "/D4_A_11") (class "Default") (node (ref "XS21") (pin "40") (pintype "passive")))
    (net (code "217") (name "/D4_A_12") (class "Default") (node (ref "XS23") (pin "40") (pintype "passive")))
    (net (code "218") (name "/D4_B_1") (class "Default") (node (ref "XS1") (pin "9") (pintype "passive")))
    (net (code "219") (name "/D4_B_2") (class "Default") (node (ref "XS3") (pin "9") (pintype "passive")))
    (net (code "220") (name "/D4_B_3") (class "Default") (node (ref "XS5") (pin "9") (pintype "passive")))
    (net (code "221") (name "/D4_B_4") (class "Default") (node (ref "XS7") (pin "9") (pintype "passive")))
    (net (code "222") (name "/D4_B_5") (class "Default") (node (ref "XS9") (pin "9") (pintype "passive")))
    (net (code "223") (name "/D4_B_6") (class "Default") (node (ref "XS11") (pin "9") (pintype "passive")))
    (net (code "224") (name "/D4_B_7") (class "Default") (node (ref "XS13") (pin "9") (pintype "passive")))
    (net (code "225") (name "/D4_B_8") (class "Default") (node (ref "XS15") (pin "9") (pintype "passive")))
    (net (code "226") (name "/D4_B_9") (class "Default") (node (ref "XS17") (pin "9") (pintype "passive")))
    (net (code "227") (name "/D4_B_10") (class "Default") (node (ref "XS19") (pin "9") (pintype "passive")))
    (net (code "228") (name "/D4_B_11") (class "Default") (node (ref "XS21") (pin "9") (pintype "passive")))
    (net (code "229") (name "/D4_B_12") (class "Default") (node (ref "XS23") (pin "9") (pintype "passive")))
    (net (code "230") (name "/D4_C_1") (class "Default") (node (ref "XS2") (pin "49") (pintype "passive")))
    (net (code "231") (name "/D4_C_2") (class "Default") (node (ref "XS4") (pin "49") (pintype "passive")))
    (net (code "232") (name "/D4_C_3") (class "Default") (node (ref "XS6") (pin "49") (pintype "passive")))
    (net (code "233") (name "/D4_C_4") (class "Default") (node (ref "XS8") (pin "49") (pintype "passive")))
    (net (code "234") (name "/D4_C_5") (class "Default") (node (ref "XS10") (pin "49") (pintype "passive")))
    (net (code "235") (name "/D4_C_6") (class "Default") (node (ref "XS12") (pin "49") (pintype "passive")))
    (net (code "236") (name "/D4_C_7") (class "Default") (node (ref "XS14") (pin "49") (pintype "passive")))
    (net (code "237") (name "/D4_C_8") (class "Default") (node (ref "XS16") (pin "49") (pintype "passive")))
    (net (code "238") (name "/D4_C_9") (class "Default") (node (ref "XS18") (pin "49") (pintype "passive")))
    (net (code "239") (name "/D4_C_10") (class "Default") (node (ref "XS20") (pin "49") (pintype "passive")))
    (net (code "240") (name "/D4_C_11") (class "Default") (node (ref "XS22") (pin "49") (pintype "passive")))
    (net (code "241") (name "/D4_C_12") (class "Default") (node (ref "XS24") (pin "49") (pintype "passive")))
    (net (code "242") (name "/D4_D_1") (class "Default") (node (ref "XS2") (pin "5") (pintype "passive")))
    (net (code "243") (name "/D4_D_2") (class "Default") (node (ref "XS4") (pin "5") (pintype "passive")))
    (net (code "244") (name "/D4_D_3") (class "Default") (node (ref "XS6") (pin "5") (pintype "passive")))
    (net (code "245") (name "/D4_D_4") (class "Default") (node (ref "XS8") (pin "5") (pintype "passive")))
    (net (code "246") (name "/D4_D_5") (class "Default") (node (ref "XS10") (pin "5") (pintype "passive")))
    (net (code "247") (name "/D4_D_6") (class "Default") (node (ref "XS12") (pin "5") (pintype "passive")))
    (net (code "248") (name "/D4_D_7") (class "Default") (node (ref "XS14") (pin "5") (pintype "passive")))
    (net (code "249") (name "/D4_D_8") (class "Default") (node (ref "XS16") (pin "5") (pintype "passive")))
    (net (code "250") (name "/D4_D_9") (class "Default") (node (ref "XS18") (pin "5") (pintype "passive")))
    (net (code "251") (name "/D4_D_10") (class "Default") (node (ref "XS20") (pin "5") (pintype "passive")))
    (net (code "252") (name "/D4_D_11") (class "Default") (node (ref "XS22") (pin "5") (pintype "passive")))
    (net (code "253") (name "/D4_D_12") (class "Default") (node (ref "XS24") (pin "5") (pintype "passive")))
    (net (code "254") (name "/D5_A_1") (class "Default") (node (ref "XS1") (pin "3") (pintype "passive")))
    (net (code "255") (name "/D5_A_2") (class "Default") (node (ref "XS3") (pin "3") (pintype "passive")))
    (net (code "256") (name "/D5_A_3") (class "Default") (node (ref "XS5") (pin "3") (pintype "passive")))
    (net (code "257") (name "/D5_A_4") (class "Default") (node (ref "XS7") (pin "3") (pintype "passive")))
    (net (code "258") (name "/D5_A_5") (class "Default") (node (ref "XS9") (pin "3") (pintype "passive")))
    (net (code "259") (name "/D5_A_6") (class "Default") (node (ref "XS11") (pin "3") (pintype "passive")))
    (net (code "260") (name "/D5_A_7") (class "Default") (node (ref "XS13") (pin "3") (pintype "passive")))
    (net (code "261") (name "/D5_A_8") (class "Default") (node (ref "XS15") (pin "3") (pintype "passive")))
    (net (code "262") (name "/D5_A_9") (class "Default") (node (ref "XS17") (pin "3") (pintype "passive")))
    (net (code "263") (name "/D5_A_10") (class "Default") (node (ref "XS19") (pin "3") (pintype "passive")))
    (net (code "264") (name "/D5_A_11") (class "Default") (node (ref "XS21") (pin "3") (pintype "passive")))
    (net (code "265") (name "/D5_A_12") (class "Default") (node (ref "XS23") (pin "3") (pintype "passive")))
    (net (code "266") (name "/D5_B_1") (class "Default") (node (ref "XS1") (pin "34") (pintype "passive")))
    (net (code "267") (name "/D5_B_2") (class "Default") (node (ref "XS3") (pin "34") (pintype "passive")))
    (net (code "268") (name "/D5_B_3") (class "Default") (node (ref "XS5") (pin "34") (pintype "passive")))
    (net (code "269") (name "/D5_B_4") (class "Default") (node (ref "XS7") (pin "34") (pintype "passive")))
    (net (code "270") (name "/D5_B_5") (class "Default") (node (ref "XS9") (pin "34") (pintype "passive")))
    (net (code "271") (name "/D5_B_6") (class "Default") (node (ref "XS11") (pin "34") (pintype "passive")))
    (net (code "272") (name "/D5_B_7") (class "Default") (node (ref "XS13") (pin "34") (pintype "passive")))
    (net (code "273") (name "/D5_B_8") (class "Default") (node (ref "XS15") (pin "34") (pintype "passive")))
    (net (code "274") (name "/D5_B_9") (class "Default") (node (ref "XS17") (pin "34") (pintype "passive")))
    (net (code "275") (name "/D5_B_10") (class "Default") (node (ref "XS19") (pin "34") (pintype "passive")))
    (net (code "276") (name "/D5_B_11") (class "Default") (node (ref "XS21") (pin "34") (pintype "passive")))
    (net (code "277") (name "/D5_B_12") (class "Default") (node (ref "XS23") (pin "34") (pintype "passive")))
    (net (code "278") (name "/D5_C_1") (class "Default") (node (ref "XS2") (pin "11") (pintype "passive")))
    (net (code "279") (name "/D5_C_2") (class "Default") (node (ref "XS4") (pin "11") (pintype "passive")))
    (net (code "280") (name "/D5_C_3") (class "Default") (node (ref "XS6") (pin "11") (pintype "passive")))
    (net (code "281") (name "/D5_C_4") (class "Default") (node (ref "XS8") (pin "11") (pintype "passive")))
    (net (code "282") (name "/D5_C_5") (class "Default") (node (ref "XS10") (pin "11") (pintype "passive")))
    (net (code "283") (name "/D5_C_6") (class "Default") (node (ref "XS12") (pin "11") (pintype "passive")))
    (net (code "284") (name "/D5_C_7") (class "Default") (node (ref "XS14") (pin "11") (pintype "passive")))
    (net (code "285") (name "/D5_C_8") (class "Default") (node (ref "XS16") (pin "11") (pintype "passive")))
    (net (code "286") (name "/D5_C_9") (class "Default") (node (ref "XS18") (pin "11") (pintype "passive")))
    (net (code "287") (name "/D5_C_10") (class "Default") (node (ref "XS20") (pin "11") (pintype "passive")))
    (net (code "288") (name "/D5_C_11") (class "Default") (node (ref "XS22") (pin "11") (pintype "passive")))
    (net (code "289") (name "/D5_C_12") (class "Default") (node (ref "XS24") (pin "11") (pintype "passive")))
    (net (code "290") (name "/D5_D_1") (class "Default") (node (ref "XS2") (pin "30") (pintype "passive")))
    (net (code "291") (name "/D5_D_2") (class "Default") (node (ref "XS4") (pin "30") (pintype "passive")))
    (net (code "292") (name "/D5_D_3") (class "Default") (node (ref "XS6") (pin "30") (pintype "passive")))
    (net (code "293") (name "/D5_D_4") (class "Default") (node (ref "XS8") (pin "30") (pintype "passive")))
    (net (code "294") (name "/D5_D_5") (class "Default") (node (ref "XS10") (pin "30") (pintype "passive")))
    (net (code "295") (name "/D5_D_6") (class "Default") (node (ref "XS12") (pin "30") (pintype "passive")))
    (net (code "296") (name "/D5_D_7") (class "Default") (node (ref "XS14") (pin "30") (pintype "passive")))
    (net (code "297") (name "/D5_D_8") (class "Default") (node (ref "XS16") (pin "30") (pintype "passive")))
    (net (code "298") (name "/D5_D_9") (class "Default") (node (ref "XS18") (pin "30") (pintype "passive")))
    (net (code "299") (name "/D5_D_10") (class "Default") (node (ref "XS20") (pin "30") (pintype "passive")))
    (net (code "300") (name "/D5_D_11") (class "Default") (node (ref "XS22") (pin "30") (pintype "passive")))
    (net (code "301") (name "/D5_D_12") (class "Default") (node (ref "XS24") (pin "30") (pintype "passive")))
    (net (code "302") (name "/D6_A_1") (class "Default") (node (ref "XS1") (pin "41") (pintype "passive")))
    (net (code "303") (name "/D6_A_2") (class "Default") (node (ref "XS3") (pin "41") (pintype "passive")))
    (net (code "304") (name "/D6_A_3") (class "Default") (node (ref "XS5") (pin "41") (pintype "passive")))
    (net (code "305") (name "/D6_A_4") (class "Default") (node (ref "XS7") (pin "41") (pintype "passive")))
    (net (code "306") (name "/D6_A_5") (class "Default") (node (ref "XS9") (pin "41") (pintype "passive")))
    (net (code "307") (name "/D6_A_6") (class "Default") (node (ref "XS11") (pin "41") (pintype "passive")))
    (net (code "308") (name "/D6_A_7") (class "Default") (node (ref "XS13") (pin "41") (pintype "passive")))
    (net (code "309") (name "/D6_A_8") (class "Default") (node (ref "XS15") (pin "41") (pintype "passive")))
    (net (code "310") (name "/D6_A_9") (class "Default") (node (ref "XS17") (pin "41") (pintype "passive")))
    (net (code "311") (name "/D6_A_10") (class "Default") (node (ref "XS19") (pin "41") (pintype "passive")))
    (net (code "312") (name "/D6_A_11") (class "Default") (node (ref "XS21") (pin "41") (pintype "passive")))
    (net (code "313") (name "/D6_A_12") (class "Default") (node (ref "XS23") (pin "41") (pintype "passive")))
    (net (code "314") (name "/D6_B_1") (class "Default") (node (ref "XS1") (pin "10") (pintype "passive")))
    (net (code "315") (name "/D6_B_2") (class "Default") (node (ref "XS3") (pin "10") (pintype "passive")))
    (net (code "316") (name "/D6_B_3") (class "Default") (node (ref "XS5") (pin "10") (pintype "passive")))
    (net (code "317") (name "/D6_B_4") (class "Default") (node (ref "XS7") (pin "10") (pintype "passive")))
    (net (code "318") (name "/D6_B_5") (class "Default") (node (ref "XS9") (pin "10") (pintype "passive")))
    (net (code "319") (name "/D6_B_6") (class "Default") (node (ref "XS11") (pin "10") (pintype "passive")))
    (net (code "320") (name "/D6_B_7") (class "Default") (node (ref "XS13") (pin "10") (pintype "passive")))
    (net (code "321") (name "/D6_B_8") (class "Default") (node (ref "XS15") (pin "10") (pintype "passive")))
    (net (code "322") (name "/D6_B_9") (class "Default") (node (ref "XS17") (pin "10") (pintype "passive")))
    (net (code "323") (name "/D6_B_10") (class "Default") (node (ref "XS19") (pin "10") (pintype "passive")))
    (net (code "324") (name "/D6_B_11") (class "Default") (node (ref "XS21") (pin "10") (pintype "passive")))
    (net (code "325") (name "/D6_B_12") (class "Default") (node (ref "XS23") (pin "10") (pintype "passive")))
    (net (code "326") (name "/D6_C_1") (class "Default") (node (ref "XS2") (pin "48") (pintype "passive")))
    (net (code "327") (name "/D6_C_2") (class "Default") (node (ref "XS4") (pin "48") (pintype "passive")))
    (net (code "328") (name "/D6_C_3") (class "Default") (node (ref "XS6") (pin "48") (pintype "passive")))
    (net (code "329") (name "/D6_C_4") (class "Default") (node (ref "XS8") (pin "48") (pintype "passive")))
    (net (code "330") (name "/D6_C_5") (class "Default") (node (ref "XS10") (pin "48") (pintype "passive")))
    (net (code "331") (name "/D6_C_6") (class "Default") (node (ref "XS12") (pin "48") (pintype "passive")))
    (net (code "332") (name "/D6_C_7") (class "Default") (node (ref "XS14") (pin "48") (pintype "passive")))
    (net (code "333") (name "/D6_C_8") (class "Default") (node (ref "XS16") (pin "48") (pintype "passive")))
    (net (code "334") (name "/D6_C_9") (class "Default") (node (ref "XS18") (pin "48") (pintype "passive")))
    (net (code "335") (name "/D6_C_10") (class "Default") (node (ref "XS20") (pin "48") (pintype "passive")))
    (net (code "336") (name "/D6_C_11") (class "Default") (node (ref "XS22") (pin "48") (pintype "passive")))
    (net (code "337") (name "/D6_C_12") (class "Default") (node (ref "XS24") (pin "48") (pintype "passive")))
    (net (code "338") (name "/D6_D_1") (class "Default") (node (ref "XS2") (pin "4") (pintype "passive")))
    (net (code "339") (name "/D6_D_2") (class "Default") (node (ref "XS4") (pin "4") (pintype "passive")))
    (net (code "340") (name "/D6_D_3") (class "Default") (node (ref "XS6") (pin "4") (pintype "passive")))
    (net (code "341") (name "/D6_D_4") (class "Default") (node (ref "XS8") (pin "4") (pintype "passive")))
    (net (code "342") (name "/D6_D_5") (class "Default") (node (ref "XS10") (pin "4") (pintype "passive")))
    (net (code "343") (name "/D6_D_6") (class "Default") (node (ref "XS12") (pin "4") (pintype "passive")))
    (net (code "344") (name "/D6_D_7") (class "Default") (node (ref "XS14") (pin "4") (pintype "passive")))
    (net (code "345") (name "/D6_D_8") (class "Default") (node (ref "XS16") (pin "4") (pintype "passive")))
    (net (code "346") (name "/D6_D_9") (class "Default") (node (ref "XS18") (pin "4") (pintype "passive")))
    (net (code "347") (name "/D6_D_10") (class "Default") (node (ref "XS20") (pin "4") (pintype "passive")))
    (net (code "348") (name "/D6_D_11") (class "Default") (node (ref "XS22") (pin "4") (pintype "passive")))
    (net (code "349") (name "/D6_D_12") (class "Default") (node (ref "XS24") (pin "4") (pintype "passive")))
    (net (code "350") (name "/D7_A_1") (class "Default") (node (ref "XS1") (pin "2") (pintype "passive")))
    (net (code "351") (name "/D7_A_2") (class "Default") (node (ref "XS3") (pin "2") (pintype "passive")))
    (net (code "352") (name "/D7_A_3") (class "Default") (node (ref "XS5") (pin "2") (pintype "passive")))
    (net (code "353") (name "/D7_A_4") (class "Default") (node (ref "XS7") (pin "2") (pintype "passive")))
    (net (code "354") (name "/D7_A_5") (class "Default") (node (ref "XS9") (pin "2") (pintype "passive")))
    (net (code "355") (name "/D7_A_6") (class "Default") (node (ref "XS11") (pin "2") (pintype "passive")))
    (net (code "356") (name "/D7_A_7") (class "Default") (node (ref "XS13") (pin "2") (pintype "passive")))
    (net (code "357") (name "/D7_A_8") (class "Default") (node (ref "XS15") (pin "2") (pintype "passive")))
    (net (code "358") (name "/D7_A_9") (class "Default") (node (ref "XS17") (pin "2") (pintype "passive")))
    (net (code "359") (name "/D7_A_10") (class "Default") (node (ref "XS19") (pin "2") (pintype "passive")))
    (net (code "360") (name "/D7_A_11") (class "Default") (node (ref "XS21") (pin "2") (pintype "passive")))
    (net (code "361") (name "/D7_A_12") (class "Default") (node (ref "XS23") (pin "2") (pintype "passive")))
    (net (code "362") (name "/D7_B_1") (class "Default") (node (ref "XS1") (pin "33") (pintype "passive")))
    (net (code "363") (name "/D7_B_2") (class "Default") (node (ref "XS3") (pin "33") (pintype "passive")))
    (net (code "364") (name "/D7_B_3") (class "Default") (node (ref "XS5") (pin "33") (pintype "passive")))
    (net (code "365") (name "/D7_B_4") (class "Default") (node (ref "XS7") (pin "33") (pintype "passive")))
    (net (code "366") (name "/D7_B_5") (class "Default") (node (ref "XS9") (pin "33") (pintype "passive")))
    (net (code "367") (name "/D7_B_6") (class "Default") (node (ref "XS11") (pin "33") (pintype "passive")))
    (net (code "368") (name "/D7_B_7") (class "Default") (node (ref "XS13") (pin "33") (pintype "passive")))
    (net (code "369") (name "/D7_B_8") (class "Default") (node (ref "XS15") (pin "33") (pintype "passive")))
    (net (code "370") (name "/D7_B_9") (class "Default") (node (ref "XS17") (pin "33") (pintype "passive")))
    (net (code "371") (name "/D7_B_10") (class "Default") (node (ref "XS19") (pin "33") (pintype "passive")))
    (net (code "372") (name "/D7_B_11") (class "Default") (node (ref "XS21") (pin "33") (pintype "passive")))
    (net (code "373") (name "/D7_B_12") (class "Default") (node (ref "XS23") (pin "33") (pintype "passive")))
    (net (code "374") (name "/D7_C_1") (class "Default") (node (ref "XS2") (pin "12") (pintype "passive")))
    (net (code "375") (name "/D7_C_2") (class "Default") (node (ref "XS4") (pin "12") (pintype "passive")))
    (net (code "376") (name "/D7_C_3") (class "Default") (node (ref "XS6") (pin "12") (pintype "passive")))
    (net (code "377") (name "/D7_C_4") (class "Default") (node (ref "XS8") (pin "12") (pintype "passive")))
    (net (code "378") (name "/D7_C_5") (class "Default") (node (ref "XS10") (pin "12") (pintype "passive")))
    (net (code "379") (name "/D7_C_6") (class "Default") (node (ref "XS12") (pin "12") (pintype "passive")))
    (net (code "380") (name "/D7_C_7") (class "Default") (node (ref "XS14") (pin "12") (pintype "passive")))
    (net (code "381") (name "/D7_C_8") (class "Default") (node (ref "XS16") (pin "12") (pintype "passive")))
    (net (code "382") (name "/D7_C_9") (class "Default") (node (ref "XS18") (pin "12") (pintype "passive")))
    (net (code "383") (name "/D7_C_10") (class "Default") (node (ref "XS20") (pin "12") (pintype "passive")))
    (net (code "384") (name "/D7_C_11") (class "Default") (node (ref "XS22") (pin "12") (pintype "passive")))
    (net (code "385") (name "/D7_C_12") (class "Default") (node (ref "XS24") (pin "12") (pintype "passive")))
    (net (code "386") (name "/D7_D_1") (class "Default") (node (ref "XS2") (pin "31") (pintype "passive")))
    (net (code "387") (name "/D7_D_2") (class "Default") (node (ref "XS4") (pin "31") (pintype "passive")))
    (net (code "388") (name "/D7_D_3") (class "Default") (node (ref "XS6") (pin "31") (pintype "passive")))
    (net (code "389") (name "/D7_D_4") (class "Default") (node (ref "XS8") (pin "31") (pintype "passive")))
    (net (code "390") (name "/D7_D_5") (class "Default") (node (ref "XS10") (pin "31") (pintype "passive")))
    (net (code "391") (name "/D7_D_6") (class "Default") (node (ref "XS12") (pin "31") (pintype "passive")))
    (net (code "392") (name "/D7_D_7") (class "Default") (node (ref "XS14") (pin "31") (pintype "passive")))
    (net (code "393") (name "/D7_D_8") (class "Default") (node (ref "XS16") (pin "31") (pintype "passive")))
    (net (code "394") (name "/D7_D_9") (class "Default") (node (ref "XS18") (pin "31") (pintype "passive")))
    (net (code "395") (name "/D7_D_10") (class "Default") (node (ref "XS20") (pin "31") (pintype "passive")))
    (net (code "396") (name "/D7_D_11") (class "Default") (node (ref "XS22") (pin "31") (pintype "passive")))
    (net (code "397") (name "/D7_D_12") (class "Default") (node (ref "XS24") (pin "31") (pintype "passive")))
    (net (code "398") (name "/D8_A_1") (class "Default") (node (ref "XS1") (pin "26") (pintype "passive")))
    (net (code "399") (name "/D8_A_2") (class "Default") (node (ref "XS3") (pin "26") (pintype "passive")))
    (net (code "400") (name "/D8_A_3") (class "Default") (node (ref "XS5") (pin "26") (pintype "passive")))
    (net (code "401") (name "/D8_A_4") (class "Default") (node (ref "XS7") (pin "26") (pintype "passive")))
    (net (code "402") (name "/D8_A_5") (class "Default") (node (ref "XS9") (pin "26") (pintype "passive")))
    (net (code "403") (name "/D8_A_6") (class "Default") (node (ref "XS11") (pin "26") (pintype "passive")))
    (net (code "404") (name "/D8_A_7") (class "Default") (node (ref "XS13") (pin "26") (pintype "passive")))
    (net (code "405") (name "/D8_A_8") (class "Default") (node (ref "XS15") (pin "26") (pintype "passive")))
    (net (code "406") (name "/D8_A_9") (class "Default") (node (ref "XS17") (pin "26") (pintype "passive")))
    (net (code "407") (name "/D8_A_10") (class "Default") (node (ref "XS19") (pin "26") (pintype "passive")))
    (net (code "408") (name "/D8_A_11") (class "Default") (node (ref "XS21") (pin "26") (pintype "passive")))
    (net (code "409") (name "/D8_A_12") (class "Default") (node (ref "XS23") (pin "26") (pintype "passive")))
    (net (code "410") (name "/D8_B_1") (class "Default") (node (ref "XS1") (pin "20") (pintype "passive")))
    (net (code "411") (name "/D8_B_2") (class "Default") (node (ref "XS3") (pin "20") (pintype "passive")))
    (net (code "412") (name "/D8_B_3") (class "Default") (node (ref "XS5") (pin "20") (pintype "passive")))
    (net (code "413") (name "/D8_B_4") (class "Default") (node (ref "XS7") (pin "20") (pintype "passive")))
    (net (code "414") (name "/D8_B_5") (class "Default") (node (ref "XS9") (pin "20") (pintype "passive")))
    (net (code "415") (name "/D8_B_6") (class "Default") (node (ref "XS11") (pin "20") (pintype "passive")))
    (net (code "416") (name "/D8_B_7") (class "Default") (node (ref "XS13") (pin "20") (pintype "passive")))
    (net (code "417") (name "/D8_B_8") (class "Default") (node (ref "XS15") (pin "20") (pintype "passive")))
    (net (code "418") (name "/D8_B_9") (class "Default") (node (ref "XS17") (pin "20") (pintype "passive")))
    (net (code "419") (name "/D8_B_10") (class "Default") (node (ref "XS19") (pin "20") (pintype "passive")))
    (net (code "420") (name "/D8_B_11") (class "Default") (node (ref "XS21") (pin "20") (pintype "passive")))
    (net (code "421") (name "/D8_B_12") (class "Default") (node (ref "XS23") (pin "20") (pintype "passive")))
    (net (code "422") (name "/D8_C_1") (class "Default") (node (ref "XS2") (pin "38") (pintype "passive")))
    (net (code "423") (name "/D8_C_2") (class "Default") (node (ref "XS4") (pin "38") (pintype "passive")))
    (net (code "424") (name "/D8_C_3") (class "Default") (node (ref "XS6") (pin "38") (pintype "passive")))
    (net (code "425") (name "/D8_C_4") (class "Default") (node (ref "XS8") (pin "38") (pintype "passive")))
    (net (code "426") (name "/D8_C_5") (class "Default") (node (ref "XS10") (pin "38") (pintype "passive")))
    (net (code "427") (name "/D8_C_6") (class "Default") (node (ref "XS12") (pin "38") (pintype "passive")))
    (net (code "428") (name "/D8_C_7") (class "Default") (node (ref "XS14") (pin "38") (pintype "passive")))
    (net (code "429") (name "/D8_C_8") (class "Default") (node (ref "XS16") (pin "38") (pintype "passive")))
    (net (code "430") (name "/D8_C_9") (class "Default") (node (ref "XS18") (pin "38") (pintype "passive")))
    (net (code "431") (name "/D8_C_10") (class "Default") (node (ref "XS20") (pin "38") (pintype "passive")))
    (net (code "432") (name "/D8_C_11") (class "Default") (node (ref "XS22") (pin "38") (pintype "passive")))
    (net (code "433") (name "/D8_C_12") (class "Default") (node (ref "XS24") (pin "38") (pintype "passive")))
    (net (code "434") (name "/D8_D_1") (class "Default") (node (ref "XS2") (pin "19") (pintype "passive")))
    (net (code "435") (name "/D8_D_2") (class "Default") (node (ref "XS4") (pin "19") (pintype "passive")))
    (net (code "436") (name "/D8_D_3") (class "Default") (node (ref "XS6") (pin "19") (pintype "passive")))
    (net (code "437") (name "/D8_D_4") (class "Default") (node (ref "XS8") (pin "19") (pintype "passive")))
    (net (code "438") (name "/D8_D_5") (class "Default") (node (ref "XS10") (pin "19") (pintype "passive")))
    (net (code "439") (name "/D8_D_6") (class "Default") (node (ref "XS12") (pin "19") (pintype "passive")))
    (net (code "440") (name "/D8_D_7") (class "Default") (node (ref "XS14") (pin "19") (pintype "passive")))
    (net (code "441") (name "/D8_D_8") (class "Default") (node (ref "XS16") (pin "19") (pintype "passive")))
    (net (code "442") (name "/D8_D_9") (class "Default") (node (ref "XS18") (pin "19") (pintype "passive")))
    (net (code "443") (name "/D8_D_10") (class "Default") (node (ref "XS20") (pin "19") (pintype "passive")))
    (net (code "444") (name "/D8_D_11") (class "Default") (node (ref "XS22") (pin "19") (pintype "passive")))
    (net (code "445") (name "/D8_D_12") (class "Default") (node (ref "XS24") (pin "19") (pintype "passive")))
    (net (code "446") (name "/D9_A_1") (class "Default") (node (ref "XS1") (pin "17") (pintype "passive")))
    (net (code "447") (name "/D9_A_2") (class "Default") (node (ref "XS3") (pin "17") (pintype "passive")))
    (net (code "448") (name "/D9_A_3") (class "Default") (node (ref "XS5") (pin "17") (pintype "passive")))
    (net (code "449") (name "/D9_A_4") (class "Default") (node (ref "XS7") (pin "17") (pintype "passive")))
    (net (code "450") (name "/D9_A_5") (class "Default") (node (ref "XS9") (pin "17") (pintype "passive")))
    (net (code "451") (name "/D9_A_6") (class "Default") (node (ref "XS11") (pin "17") (pintype "passive")))
    (net (code "452") (name "/D9_A_7") (class "Default") (node (ref "XS13") (pin "17") (pintype "passive")))
    (net (code "453") (name "/D9_A_8") (class "Default") (node (ref "XS15") (pin "17") (pintype "passive")))
    (net (code "454") (name "/D9_A_9") (class "Default") (node (ref "XS17") (pin "17") (pintype "passive")))
    (net (code "455") (name "/D9_A_10") (class "Default") (node (ref "XS19") (pin "17") (pintype "passive")))
    (net (code "456") (name "/D9_A_11") (class "Default") (node (ref "XS21") (pin "17") (pintype "passive")))
    (net (code "457") (name "/D9_A_12") (class "Default") (node (ref "XS23") (pin "17") (pintype "passive")))
    (net (code "458") (name "/D9_B_1") (class "Default") (node (ref "XS1") (pin "48") (pintype "passive")))
    (net (code "459") (name "/D9_B_2") (class "Default") (node (ref "XS3") (pin "48") (pintype "passive")))
    (net (code "460") (name "/D9_B_3") (class "Default") (node (ref "XS5") (pin "48") (pintype "passive")))
    (net (code "461") (name "/D9_B_4") (class "Default") (node (ref "XS7") (pin "48") (pintype "passive")))
    (net (code "462") (name "/D9_B_5") (class "Default") (node (ref "XS9") (pin "48") (pintype "passive")))
    (net (code "463") (name "/D9_B_6") (class "Default") (node (ref "XS11") (pin "48") (pintype "passive")))
    (net (code "464") (name "/D9_B_7") (class "Default") (node (ref "XS13") (pin "48") (pintype "passive")))
    (net (code "465") (name "/D9_B_8") (class "Default") (node (ref "XS15") (pin "48") (pintype "passive")))
    (net (code "466") (name "/D9_B_9") (class "Default") (node (ref "XS17") (pin "48") (pintype "passive")))
    (net (code "467") (name "/D9_B_10") (class "Default") (node (ref "XS19") (pin "48") (pintype "passive")))
    (net (code "468") (name "/D9_B_11") (class "Default") (node (ref "XS21") (pin "48") (pintype "passive")))
    (net (code "469") (name "/D9_B_12") (class "Default") (node (ref "XS23") (pin "48") (pintype "passive")))
    (net (code "470") (name "/D9_C_1") (class "Default") (node (ref "XS2") (pin "22") (pintype "passive")))
    (net (code "471") (name "/D9_C_2") (class "Default") (node (ref "XS4") (pin "22") (pintype "passive")))
    (net (code "472") (name "/D9_C_3") (class "Default") (node (ref "XS6") (pin "22") (pintype "passive")))
    (net (code "473") (name "/D9_C_4") (class "Default") (node (ref "XS8") (pin "22") (pintype "passive")))
    (net (code "474") (name "/D9_C_5") (class "Default") (node (ref "XS10") (pin "22") (pintype "passive")))
    (net (code "475") (name "/D9_C_6") (class "Default") (node (ref "XS12") (pin "22") (pintype "passive")))
    (net (code "476") (name "/D9_C_7") (class "Default") (node (ref "XS14") (pin "22") (pintype "passive")))
    (net (code "477") (name "/D9_C_8") (class "Default") (node (ref "XS16") (pin "22") (pintype "passive")))
    (net (code "478") (name "/D9_C_9") (class "Default") (node (ref "XS18") (pin "22") (pintype "passive")))
    (net (code "479") (name "/D9_C_10") (class "Default") (node (ref "XS20") (pin "22") (pintype "passive")))
    (net (code "480") (name "/D9_C_11") (class "Default") (node (ref "XS22") (pin "22") (pintype "passive")))
    (net (code "481") (name "/D9_C_12") (class "Default") (node (ref "XS24") (pin "22") (pintype "passive")))
    (net (code "482") (name "/D9_D_1") (class "Default") (node (ref "XS2") (pin "41") (pintype "passive")))
    (net (code "483") (name "/D9_D_2") (class "Default") (node (ref "XS4") (pin "41") (pintype "passive")))
    (net (code "484") (name "/D9_D_3") (class "Default") (node (ref "XS6") (pin "41") (pintype "passive")))
    (net (code "485") (name "/D9_D_4") (class "Default") (node (ref "XS8") (pin "41") (pintype "passive")))
    (net (code "486") (name "/D9_D_5") (class "Default") (node (ref "XS10") (pin "41") (pintype "passive")))
    (net (code "487") (name "/D9_D_6") (class "Default") (node (ref "XS12") (pin "41") (pintype "passive")))
    (net (code "488") (name "/D9_D_7") (class "Default") (node (ref "XS14") (pin "41") (pintype "passive")))
    (net (code "489") (name "/D9_D_8") (class "Default") (node (ref "XS16") (pin "41") (pintype "passive")))
    (net (code "490") (name "/D9_D_9") (class "Default") (node (ref "XS18") (pin "41") (pintype "passive")))
    (net (code "491") (name "/D9_D_10") (class "Default") (node (ref "XS20") (pin "41") (pintype "passive")))
    (net (code "492") (name "/D9_D_11") (class "Default") (node (ref "XS22") (pin "41") (pintype "passive")))
    (net (code "493") (name "/D9_D_12") (class "Default") (node (ref "XS24") (pin "41") (pintype "passive")))
    (net (code "494") (name "/D10_A_1") (class "Default") (node (ref "XS1") (pin "30") (pintype "passive")))
    (net (code "495") (name "/D10_A_2") (class "Default") (node (ref "XS3") (pin "30") (pintype "passive")))
    (net (code "496") (name "/D10_A_3") (class "Default") (node (ref "XS5") (pin "30") (pintype "passive")))
    (net (code "497") (name "/D10_A_4") (class "Default") (node (ref "XS7") (pin "30") (pintype "passive")))
    (net (code "498") (name "/D10_A_5") (class "Default") (node (ref "XS9") (pin "30") (pintype "passive")))
    (net (code "499") (name "/D10_A_6") (class "Default") (node (ref "XS11") (pin "30") (pintype "passive")))
    (net (code "500") (name "/D10_A_7") (class "Default") (node (ref "XS13") (pin "30") (pintype "passive")))
    (net (code "501") (name "/D10_A_8") (class "Default") (node (ref "XS15") (pin "30") (pintype "passive")))
    (net (code "502") (name "/D10_A_9") (class "Default") (node (ref "XS17") (pin "30") (pintype "passive")))
    (net (code "503") (name "/D10_A_10") (class "Default") (node (ref "XS19") (pin "30") (pintype "passive")))
    (net (code "504") (name "/D10_A_11") (class "Default") (node (ref "XS21") (pin "30") (pintype "passive")))
    (net (code "505") (name "/D10_A_12") (class "Default") (node (ref "XS23") (pin "30") (pintype "passive")))
    (net (code "506") (name "/D10_B_1") (class "Default") (node (ref "XS1") (pin "24") (pintype "passive")))
    (net (code "507") (name "/D10_B_2") (class "Default") (node (ref "XS3") (pin "24") (pintype "passive")))
    (net (code "508") (name "/D10_B_3") (class "Default") (node (ref "XS5") (pin "24") (pintype "passive")))
    (net (code "509") (name "/D10_B_4") (class "Default") (node (ref "XS7") (pin "24") (pintype "passive")))
    (net (code "510") (name "/D10_B_5") (class "Default") (node (ref "XS9") (pin "24") (pintype "passive")))
    (net (code "511") (name "/D10_B_6") (class "Default") (node (ref "XS11") (pin "24") (pintype "passive")))
    (net (code "512") (name "/D10_B_7") (class "Default") (node (ref "XS13") (pin "24") (pintype "passive")))
    (net (code "513") (name "/D10_B_8") (class "Default") (node (ref "XS15") (pin "24") (pintype "passive")))
    (net (code "514") (name "/D10_B_9") (class "Default") (node (ref "XS17") (pin "24") (pintype "passive")))
    (net (code "515") (name "/D10_B_10") (class "Default") (node (ref "XS19") (pin "24") (pintype "passive")))
    (net (code "516") (name "/D10_B_11") (class "Default") (node (ref "XS21") (pin "24") (pintype "passive")))
    (net (code "517") (name "/D10_B_12") (class "Default") (node (ref "XS23") (pin "24") (pintype "passive")))
    (net (code "518") (name "/D10_C_1") (class "Default") (node (ref "XS2") (pin "34") (pintype "passive")))
    (net (code "519") (name "/D10_C_2") (class "Default") (node (ref "XS4") (pin "34") (pintype "passive")))
    (net (code "520") (name "/D10_C_3") (class "Default") (node (ref "XS6") (pin "34") (pintype "passive")))
    (net (code "521") (name "/D10_C_4") (class "Default") (node (ref "XS8") (pin "34") (pintype "passive")))
    (net (code "522") (name "/D10_C_5") (class "Default") (node (ref "XS10") (pin "34") (pintype "passive")))
    (net (code "523") (name "/D10_C_6") (class "Default") (node (ref "XS12") (pin "34") (pintype "passive")))
    (net (code "524") (name "/D10_C_7") (class "Default") (node (ref "XS14") (pin "34") (pintype "passive")))
    (net (code "525") (name "/D10_C_8") (class "Default") (node (ref "XS16") (pin "34") (pintype "passive")))
    (net (code "526") (name "/D10_C_9") (class "Default") (node (ref "XS18") (pin "34") (pintype "passive")))
    (net (code "527") (name "/D10_C_10") (class "Default") (node (ref "XS20") (pin "34") (pintype "passive")))
    (net (code "528") (name "/D10_C_11") (class "Default") (node (ref "XS22") (pin "34") (pintype "passive")))
    (net (code "529") (name "/D10_C_12") (class "Default") (node (ref "XS24") (pin "34") (pintype "passive")))
    (net (code "530") (name "/D10_D_1") (class "Default") (node (ref "XS2") (pin "15") (pintype "passive")))
    (net (code "531") (name "/D10_D_2") (class "Default") (node (ref "XS4") (pin "15") (pintype "passive")))
    (net (code "532") (name "/D10_D_3") (class "Default") (node (ref "XS6") (pin "15") (pintype "passive")))
    (net (code "533") (name "/D10_D_4") (class "Default") (node (ref "XS8") (pin "15") (pintype "passive")))
    (net (code "534") (name "/D10_D_5") (class "Default") (node (ref "XS10") (pin "15") (pintype "passive")))
    (net (code "535") (name "/D10_D_6") (class "Default") (node (ref "XS12") (pin "15") (pintype "passive")))
    (net (code "536") (name "/D10_D_7") (class "Default") (node (ref "XS14") (pin "15") (pintype "passive")))
    (net (code "537") (name "/D10_D_8") (class "Default") (node (ref "XS16") (pin "15") (pintype "passive")))
    (net (code "538") (name "/D10_D_9") (class "Default") (node (ref "XS18") (pin "15") (pintype "passive")))
    (net (code "539") (name "/D10_D_10") (class "Default") (node (ref "XS20") (pin "15") (pintype "passive")))
    (net (code "540") (name "/D10_D_11") (class "Default") (node (ref "XS22") (pin "15") (pintype "passive")))
    (net (code "541") (name "/D10_D_12") (class "Default") (node (ref "XS24") (pin "15") (pintype "passive")))
    (net (code "542") (name "/D11_A_1") (class "Default") (node (ref "XS1") (pin "5") (pintype "passive")))
    (net (code "543") (name "/D11_A_2") (class "Default") (node (ref "XS3") (pin "5") (pintype "passive")))
    (net (code "544") (name "/D11_A_3") (class "Default") (node (ref "XS5") (pin "5") (pintype "passive")))
    (net (code "545") (name "/D11_A_4") (class "Default") (node (ref "XS7") (pin "5") (pintype "passive")))
    (net (code "546") (name "/D11_A_5") (class "Default") (node (ref "XS9") (pin "5") (pintype "passive")))
    (net (code "547") (name "/D11_A_6") (class "Default") (node (ref "XS11") (pin "5") (pintype "passive")))
    (net (code "548") (name "/D11_A_7") (class "Default") (node (ref "XS13") (pin "5") (pintype "passive")))
    (net (code "549") (name "/D11_A_8") (class "Default") (node (ref "XS15") (pin "5") (pintype "passive")))
    (net (code "550") (name "/D11_A_9") (class "Default") (node (ref "XS17") (pin "5") (pintype "passive")))
    (net (code "551") (name "/D11_A_10") (class "Default") (node (ref "XS19") (pin "5") (pintype "passive")))
    (net (code "552") (name "/D11_A_11") (class "Default") (node (ref "XS21") (pin "5") (pintype "passive")))
    (net (code "553") (name "/D11_A_12") (class "Default") (node (ref "XS23") (pin "5") (pintype "passive")))
    (net (code "554") (name "/D11_B_1") (class "Default") (node (ref "XS1") (pin "36") (pintype "passive")))
    (net (code "555") (name "/D11_B_2") (class "Default") (node (ref "XS3") (pin "36") (pintype "passive")))
    (net (code "556") (name "/D11_B_3") (class "Default") (node (ref "XS5") (pin "36") (pintype "passive")))
    (net (code "557") (name "/D11_B_4") (class "Default") (node (ref "XS7") (pin "36") (pintype "passive")))
    (net (code "558") (name "/D11_B_5") (class "Default") (node (ref "XS9") (pin "36") (pintype "passive")))
    (net (code "559") (name "/D11_B_6") (class "Default") (node (ref "XS11") (pin "36") (pintype "passive")))
    (net (code "560") (name "/D11_B_7") (class "Default") (node (ref "XS13") (pin "36") (pintype "passive")))
    (net (code "561") (name "/D11_B_8") (class "Default") (node (ref "XS15") (pin "36") (pintype "passive")))
    (net (code "562") (name "/D11_B_9") (class "Default") (node (ref "XS17") (pin "36") (pintype "passive")))
    (net (code "563") (name "/D11_B_10") (class "Default") (node (ref "XS19") (pin "36") (pintype "passive")))
    (net (code "564") (name "/D11_B_11") (class "Default") (node (ref "XS21") (pin "36") (pintype "passive")))
    (net (code "565") (name "/D11_B_12") (class "Default") (node (ref "XS23") (pin "36") (pintype "passive")))
    (net (code "566") (name "/D11_C_1") (class "Default") (node (ref "XS2") (pin "9") (pintype "passive")))
    (net (code "567") (name "/D11_C_2") (class "Default") (node (ref "XS4") (pin "9") (pintype "passive")))
    (net (code "568") (name "/D11_C_3") (class "Default") (node (ref "XS6") (pin "9") (pintype "passive")))
    (net (code "569") (name "/D11_C_4") (class "Default") (node (ref "XS8") (pin "9") (pintype "passive")))
    (net (code "570") (name "/D11_C_5") (class "Default") (node (ref "XS10") (pin "9") (pintype "passive")))
    (net (code "571") (name "/D11_C_6") (class "Default") (node (ref "XS12") (pin "9") (pintype "passive")))
    (net (code "572") (name "/D11_C_7") (class "Default") (node (ref "XS14") (pin "9") (pintype "passive")))
    (net (code "573") (name "/D11_C_8") (class "Default") (node (ref "XS16") (pin "9") (pintype "passive")))
    (net (code "574") (name "/D11_C_9") (class "Default") (node (ref "XS18") (pin "9") (pintype "passive")))
    (net (code "575") (name "/D11_C_10") (class "Default") (node (ref "XS20") (pin "9") (pintype "passive")))
    (net (code "576") (name "/D11_C_11") (class "Default") (node (ref "XS22") (pin "9") (pintype "passive")))
    (net (code "577") (name "/D11_C_12") (class "Default") (node (ref "XS24") (pin "9") (pintype "passive")))
    (net (code "578") (name "/D11_D_1") (class "Default") (node (ref "XS2") (pin "28") (pintype "passive")))
    (net (code "579") (name "/D11_D_2") (class "Default") (node (ref "XS4") (pin "28") (pintype "passive")))
    (net (code "580") (name "/D11_D_3") (class "Default") (node (ref "XS6") (pin "28") (pintype "passive")))
    (net (code "581") (name "/D11_D_4") (class "Default") (node (ref "XS8") (pin "28") (pintype "passive")))
    (net (code "582") (name "/D11_D_5") (class "Default") (node (ref "XS10") (pin "28") (pintype "passive")))
    (net (code "583") (name "/D11_D_6") (class "Default") (node (ref "XS12") (pin "28") (pintype "passive")))
    (net (code "584") (name "/D11_D_7") (class "Default") (node (ref "XS14") (pin "28") (pintype "passive")))
    (net (code "585") (name "/D11_D_8") (class "Default") (node (ref "XS16") (pin "28") (pintype "passive")))
    (net (code "586") (name "/D11_D_9") (class "Default") (node (ref "XS18") (pin "28") (pintype "passive")))
    (net (code "587") (name "/D11_D_10") (class "Default") (node (ref "XS20") (pin "28") (pintype "passive")))
    (net (code "588") (name "/D11_D_11") (class "Default") (node (ref "XS22") (pin "28") (pintype "passive")))
    (net (code "589") (name "/D11_D_12") (class "Default") (node (ref "XS24") (pin "28") (pintype "passive")))
    (net (code "590") (name "/D12_A_1") (class "Default") (node (ref "XS1") (pin "29") (pintype "passive")))
    (net (code "591") (name "/D12_A_2") (class "Default") (node (ref "XS3") (pin "29") (pintype "passive")))
    (net (code "592") (name "/D12_A_3") (class "Default") (node (ref "XS5") (pin "29") (pintype "passive")))
    (net (code "593") (name "/D12_A_4") (class "Default") (node (ref "XS7") (pin "29") (pintype "passive")))
    (net (code "594") (name "/D12_A_5") (class "Default") (node (ref "XS9") (pin "29") (pintype "passive")))
    (net (code "595") (name "/D12_A_6") (class "Default") (node (ref "XS11") (pin "29") (pintype "passive")))
    (net (code "596") (name "/D12_A_7") (class "Default") (node (ref "XS13") (pin "29") (pintype "passive")))
    (net (code "597") (name "/D12_A_8") (class "Default") (node (ref "XS15") (pin "29") (pintype "passive")))
    (net (code "598") (name "/D12_A_9") (class "Default") (node (ref "XS17") (pin "29") (pintype "passive")))
    (net (code "599") (name "/D12_A_10") (class "Default") (node (ref "XS19") (pin "29") (pintype "passive")))
    (net (code "600") (name "/D12_A_11") (class "Default") (node (ref "XS21") (pin "29") (pintype "passive")))
    (net (code "601") (name "/D12_A_12") (class "Default") (node (ref "XS23") (pin "29") (pintype "passive")))
    (net (code "602") (name "/D12_B_1") (class "Default") (node (ref "XS1") (pin "23") (pintype "passive")))
    (net (code "603") (name "/D12_B_2") (class "Default") (node (ref "XS3") (pin "23") (pintype "passive")))
    (net (code "604") (name "/D12_B_3") (class "Default") (node (ref "XS5") (pin "23") (pintype "passive")))
    (net (code "605") (name "/D12_B_4") (class "Default") (node (ref "XS7") (pin "23") (pintype "passive")))
    (net (code "606") (name "/D12_B_5") (class "Default") (node (ref "XS9") (pin "23") (pintype "passive")))
    (net (code "607") (name "/D12_B_6") (class "Default") (node (ref "XS11") (pin "23") (pintype "passive")))
    (net (code "608") (name "/D12_B_7") (class "Default") (node (ref "XS13") (pin "23") (pintype "passive")))
    (net (code "609") (name "/D12_B_8") (class "Default") (node (ref "XS15") (pin "23") (pintype "passive")))
    (net (code "610") (name "/D12_B_9") (class "Default") (node (ref "XS17") (pin "23") (pintype "passive")))
    (net (code "611") (name "/D12_B_10") (class "Default") (node (ref "XS19") (pin "23") (pintype "passive")))
    (net (code "612") (name "/D12_B_11") (class "Default") (node (ref "XS21") (pin "23") (pintype "passive")))
    (net (code "613") (name "/D12_B_12") (class "Default") (node (ref "XS23") (pin "23") (pintype "passive")))
    (net (code "614") (name "/D12_C_1") (class "Default") (node (ref "XS2") (pin "35") (pintype "passive")))
    (net (code "615") (name "/D12_C_2") (class "Default") (node (ref "XS4") (pin "35") (pintype "passive")))
    (net (code "616") (name "/D12_C_3") (class "Default") (node (ref "XS6") (pin "35") (pintype "passive")))
    (net (code "617") (name "/D12_C_4") (class "Default") (node (ref "XS8") (pin "35") (pintype "passive")))
    (net (code "618") (name "/D12_C_5") (class "Default") (node (ref "XS10") (pin "35") (pintype "passive")))
    (net (code "619") (name "/D12_C_6") (class "Default") (node (ref "XS12") (pin "35") (pintype "passive")))
    (net (code "620") (name "/D12_C_7") (class "Default") (node (ref "XS14") (pin "35") (pintype "passive")))
    (net (code "621") (name "/D12_C_8") (class "Default") (node (ref "XS16") (pin "35") (pintype "passive")))
    (net (code "622") (name "/D12_C_9") (class "Default") (node (ref "XS18") (pin "35") (pintype "passive")))
    (net (code "623") (name "/D12_C_10") (class "Default") (node (ref "XS20") (pin "35") (pintype "passive")))
    (net (code "624") (name "/D12_C_11") (class "Default") (node (ref "XS22") (pin "35") (pintype "passive")))
    (net (code "625") (name "/D12_C_12") (class "Default") (node (ref "XS24") (pin "35") (pintype "passive")))
    (net (code "626") (name "/D12_D_1") (class "Default") (node (ref "XS2") (pin "16") (pintype "passive")))
    (net (code "627") (name "/D12_D_2") (class "Default") (node (ref "XS4") (pin "16") (pintype "passive")))
    (net (code "628") (name "/D12_D_3") (class "Default") (node (ref "XS6") (pin "16") (pintype "passive")))
    (net (code "629") (name "/D12_D_4") (class "Default") (node (ref "XS8") (pin "16") (pintype "passive")))
    (net (code "630") (name "/D12_D_5") (class "Default") (node (ref "XS10") (pin "16") (pintype "passive")))
    (net (code "631") (name "/D12_D_6") (class "Default") (node (ref "XS12") (pin "16") (pintype "passive")))
    (net (code "632") (name "/D12_D_7") (class "Default") (node (ref "XS14") (pin "16") (pintype "passive")))
    (net (code "633") (name "/D12_D_8") (class "Default") (node (ref "XS16") (pin "16") (pintype "passive")))
    (net (code "634") (name "/D12_D_9") (class "Default") (node (ref "XS18") (pin "16") (pintype "passive")))
    (net (code "635") (name "/D12_D_10") (class "Default") (node (ref "XS20") (pin "16") (pintype "passive")))
    (net (code "636") (name "/D12_D_11") (class "Default") (node (ref "XS22") (pin "16") (pintype "passive")))
    (net (code "637") (name "/D12_D_12") (class "Default") (node (ref "XS24") (pin "16") (pintype "passive")))
    (net (code "638") (name "/D13_A_1") (class "Default") (node (ref "XS1") (pin "6") (pintype "passive")))
    (net (code "639") (name "/D13_A_2") (class "Default") (node (ref "XS3") (pin "6") (pintype "passive")))
    (net (code "640") (name "/D13_A_3") (class "Default") (node (ref "XS5") (pin "6") (pintype "passive")))
    (net (code "641") (name "/D13_A_4") (class "Default") (node (ref "XS7") (pin "6") (pintype "passive")))
    (net (code "642") (name "/D13_A_5") (class "Default") (node (ref "XS9") (pin "6") (pintype "passive")))
    (net (code "643") (name "/D13_A_6") (class "Default") (node (ref "XS11") (pin "6") (pintype "passive")))
    (net (code "644") (name "/D13_A_7") (class "Default") (node (ref "XS13") (pin "6") (pintype "passive")))
    (net (code "645") (name "/D13_A_8") (class "Default") (node (ref "XS15") (pin "6") (pintype "passive")))
    (net (code "646") (name "/D13_A_9") (class "Default") (node (ref "XS17") (pin "6") (pintype "passive")))
    (net (code "647") (name "/D13_A_10") (class "Default") (node (ref "XS19") (pin "6") (pintype "passive")))
    (net (code "648") (name "/D13_A_11") (class "Default") (node (ref "XS21") (pin "6") (pintype "passive")))
    (net (code "649") (name "/D13_A_12") (class "Default") (node (ref "XS23") (pin "6") (pintype "passive")))
    (net (code "650") (name "/D13_B_1") (class "Default") (node (ref "XS1") (pin "37") (pintype "passive")))
    (net (code "651") (name "/D13_B_2") (class "Default") (node (ref "XS3") (pin "37") (pintype "passive")))
    (net (code "652") (name "/D13_B_3") (class "Default") (node (ref "XS5") (pin "37") (pintype "passive")))
    (net (code "653") (name "/D13_B_4") (class "Default") (node (ref "XS7") (pin "37") (pintype "passive")))
    (net (code "654") (name "/D13_B_5") (class "Default") (node (ref "XS9") (pin "37") (pintype "passive")))
    (net (code "655") (name "/D13_B_6") (class "Default") (node (ref "XS11") (pin "37") (pintype "passive")))
    (net (code "656") (name "/D13_B_7") (class "Default") (node (ref "XS13") (pin "37") (pintype "passive")))
    (net (code "657") (name "/D13_B_8") (class "Default") (node (ref "XS15") (pin "37") (pintype "passive")))
    (net (code "658") (name "/D13_B_9") (class "Default") (node (ref "XS17") (pin "37") (pintype "passive")))
    (net (code "659") (name "/D13_B_10") (class "Default") (node (ref "XS19") (pin "37") (pintype "passive")))
    (net (code "660") (name "/D13_B_11") (class "Default") (node (ref "XS21") (pin "37") (pintype "passive")))
    (net (code "661") (name "/D13_B_12") (class "Default") (node (ref "XS23") (pin "37") (pintype "passive")))
    (net (code "662") (name "/D13_C_1") (class "Default") (node (ref "XS2") (pin "8") (pintype "passive")))
    (net (code "663") (name "/D13_C_2") (class "Default") (node (ref "XS4") (pin "8") (pintype "passive")))
    (net (code "664") (name "/D13_C_3") (class "Default") (node (ref "XS6") (pin "8") (pintype "passive")))
    (net (code "665") (name "/D13_C_4") (class "Default") (node (ref "XS8") (pin "8") (pintype "passive")))
    (net (code "666") (name "/D13_C_5") (class "Default") (node (ref "XS10") (pin "8") (pintype "passive")))
    (net (code "667") (name "/D13_C_6") (class "Default") (node (ref "XS12") (pin "8") (pintype "passive")))
    (net (code "668") (name "/D13_C_7") (class "Default") (node (ref "XS14") (pin "8") (pintype "passive")))
    (net (code "669") (name "/D13_C_8") (class "Default") (node (ref "XS16") (pin "8") (pintype "passive")))
    (net (code "670") (name "/D13_C_9") (class "Default") (node (ref "XS18") (pin "8") (pintype "passive")))
    (net (code "671") (name "/D13_C_10") (class "Default") (node (ref "XS20") (pin "8") (pintype "passive")))
    (net (code "672") (name "/D13_C_11") (class "Default") (node (ref "XS22") (pin "8") (pintype "passive")))
    (net (code "673") (name "/D13_C_12") (class "Default") (node (ref "XS24") (pin "8") (pintype "passive")))
    (net (code "674") (name "/D13_D_1") (class "Default") (node (ref "XS2") (pin "27") (pintype "passive")))
    (net (code "675") (name "/D13_D_2") (class "Default") (node (ref "XS4") (pin "27") (pintype "passive")))
    (net (code "676") (name "/D13_D_3") (class "Default") (node (ref "XS6") (pin "27") (pintype "passive")))
    (net (code "677") (name "/D13_D_4") (class "Default") (node (ref "XS8") (pin "27") (pintype "passive")))
    (net (code "678") (name "/D13_D_5") (class "Default") (node (ref "XS10") (pin "27") (pintype "passive")))
    (net (code "679") (name "/D13_D_6") (class "Default") (node (ref "XS12") (pin "27") (pintype "passive")))
    (net (code "680") (name "/D13_D_7") (class "Default") (node (ref "XS14") (pin "27") (pintype "passive")))
    (net (code "681") (name "/D13_D_8") (class "Default") (node (ref "XS16") (pin "27") (pintype "passive")))
    (net (code "682") (name "/D13_D_9") (class "Default") (node (ref "XS18") (pin "27") (pintype "passive")))
    (net (code "683") (name "/D13_D_10") (class "Default") (node (ref "XS20") (pin "27") (pintype "passive")))
    (net (code "684") (name "/D13_D_11") (class "Default") (node (ref "XS22") (pin "27") (pintype "passive")))
    (net (code "685") (name "/D13_D_12") (class "Default") (node (ref "XS24") (pin "27") (pintype "passive")))
    (net (code "686") (name "/D14_A_1") (class "Default") (node (ref "XS1") (pin "44") (pintype "passive")))
    (net (code "687") (name "/D14_A_2") (class "Default") (node (ref "XS3") (pin "44") (pintype "passive")))
    (net (code "688") (name "/D14_A_3") (class "Default") (node (ref "XS5") (pin "44") (pintype "passive")))
    (net (code "689") (name "/D14_A_4") (class "Default") (node (ref "XS7") (pin "44") (pintype "passive")))
    (net (code "690") (name "/D14_A_5") (class "Default") (node (ref "XS9") (pin "44") (pintype "passive")))
    (net (code "691") (name "/D14_A_6") (class "Default") (node (ref "XS11") (pin "44") (pintype "passive")))
    (net (code "692") (name "/D14_A_7") (class "Default") (node (ref "XS13") (pin "44") (pintype "passive")))
    (net (code "693") (name "/D14_A_8") (class "Default") (node (ref "XS15") (pin "44") (pintype "passive")))
    (net (code "694") (name "/D14_A_9") (class "Default") (node (ref "XS17") (pin "44") (pintype "passive")))
    (net (code "695") (name "/D14_A_10") (class "Default") (node (ref "XS19") (pin "44") (pintype "passive")))
    (net (code "696") (name "/D14_A_11") (class "Default") (node (ref "XS21") (pin "44") (pintype "passive")))
    (net (code "697") (name "/D14_A_12") (class "Default") (node (ref "XS23") (pin "44") (pintype "passive")))
    (net (code "698") (name "/D14_B_1") (class "Default") (node (ref "XS1") (pin "13") (pintype "passive")))
    (net (code "699") (name "/D14_B_2") (class "Default") (node (ref "XS3") (pin "13") (pintype "passive")))
    (net (code "700") (name "/D14_B_3") (class "Default") (node (ref "XS5") (pin "13") (pintype "passive")))
    (net (code "701") (name "/D14_B_4") (class "Default") (node (ref "XS7") (pin "13") (pintype "passive")))
    (net (code "702") (name "/D14_B_5") (class "Default") (node (ref "XS9") (pin "13") (pintype "passive")))
    (net (code "703") (name "/D14_B_6") (class "Default") (node (ref "XS11") (pin "13") (pintype "passive")))
    (net (code "704") (name "/D14_B_7") (class "Default") (node (ref "XS13") (pin "13") (pintype "passive")))
    (net (code "705") (name "/D14_B_8") (class "Default") (node (ref "XS15") (pin "13") (pintype "passive")))
    (net (code "706") (name "/D14_B_9") (class "Default") (node (ref "XS17") (pin "13") (pintype "passive")))
    (net (code "707") (name "/D14_B_10") (class "Default") (node (ref "XS19") (pin "13") (pintype "passive")))
    (net (code "708") (name "/D14_B_11") (class "Default") (node (ref "XS21") (pin "13") (pintype "passive")))
    (net (code "709") (name "/D14_B_12") (class "Default") (node (ref "XS23") (pin "13") (pintype "passive")))
    (net (code "710") (name "/D14_C_1") (class "Default") (node (ref "XS2") (pin "45") (pintype "passive")))
    (net (code "711") (name "/D14_C_2") (class "Default") (node (ref "XS4") (pin "45") (pintype "passive")))
    (net (code "712") (name "/D14_C_3") (class "Default") (node (ref "XS6") (pin "45") (pintype "passive")))
    (net (code "713") (name "/D14_C_4") (class "Default") (node (ref "XS8") (pin "45") (pintype "passive")))
    (net (code "714") (name "/D14_C_5") (class "Default") (node (ref "XS10") (pin "45") (pintype "passive")))
    (net (code "715") (name "/D14_C_6") (class "Default") (node (ref "XS12") (pin "45") (pintype "passive")))
    (net (code "716") (name "/D14_C_7") (class "Default") (node (ref "XS14") (pin "45") (pintype "passive")))
    (net (code "717") (name "/D14_C_8") (class "Default") (node (ref "XS16") (pin "45") (pintype "passive")))
    (net (code "718") (name "/D14_C_9") (class "Default") (node (ref "XS18") (pin "45") (pintype "passive")))
    (net (code "719") (name "/D14_C_10") (class "Default") (node (ref "XS20") (pin "45") (pintype "passive")))
    (net (code "720") (name "/D14_C_11") (class "Default") (node (ref "XS22") (pin "45") (pintype "passive")))
    (net (code "721") (name "/D14_C_12") (class "Default") (node (ref "XS24") (pin "45") (pintype "passive")))
    (net (code "722") (name "/D14_D_1") (class "Default") (node (ref "XS2") (pin "1") (pintype "passive")))
    (net (code "723") (name "/D14_D_2") (class "Default") (node (ref "XS4") (pin "1") (pintype "passive")))
    (net (code "724") (name "/D14_D_3") (class "Default") (node (ref "XS6") (pin "1") (pintype "passive")))
    (net (code "725") (name "/D14_D_4") (class "Default") (node (ref "XS8") (pin "1") (pintype "passive")))
    (net (code "726") (name "/D14_D_5") (class "Default") (node (ref "XS10") (pin "1") (pintype "passive")))
    (net (code "727") (name "/D14_D_6") (class "Default") (node (ref "XS12") (pin "1") (pintype "passive")))
    (net (code "728") (name "/D14_D_7") (class "Default") (node (ref "XS14") (pin "1") (pintype "passive")))
    (net (code "729") (name "/D14_D_8") (class "Default") (node (ref "XS16") (pin "1") (pintype "passive")))
    (net (code "730") (name "/D14_D_9") (class "Default") (node (ref "XS18") (pin "1") (pintype "passive")))
    (net (code "731") (name "/D14_D_10") (class "Default") (node (ref "XS20") (pin "1") (pintype "passive")))
    (net (code "732") (name "/D14_D_11") (class "Default") (node (ref "XS22") (pin "1") (pintype "passive")))
    (net (code "733") (name "/D14_D_12") (class "Default") (node (ref "XS24") (pin "1") (pintype "passive")))
    (net (code "734") (name "/D15_A_1") (class "Default") (node (ref "XS1") (pin "43") (pintype "passive")))
    (net (code "735") (name "/D15_A_2") (class "Default") (node (ref "XS3") (pin "43") (pintype "passive")))
    (net (code "736") (name "/D15_A_3") (class "Default") (node (ref "XS5") (pin "43") (pintype "passive")))
    (net (code "737") (name "/D15_A_4") (class "Default") (node (ref "XS7") (pin "43") (pintype "passive")))
    (net (code "738") (name "/D15_A_5") (class "Default") (node (ref "XS9") (pin "43") (pintype "passive")))
    (net (code "739") (name "/D15_A_6") (class "Default") (node (ref "XS11") (pin "43") (pintype "passive")))
    (net (code "740") (name "/D15_A_7") (class "Default") (node (ref "XS13") (pin "43") (pintype "passive")))
    (net (code "741") (name "/D15_A_8") (class "Default") (node (ref "XS15") (pin "43") (pintype "passive")))
    (net (code "742") (name "/D15_A_9") (class "Default") (node (ref "XS17") (pin "43") (pintype "passive")))
    (net (code "743") (name "/D15_A_10") (class "Default") (node (ref "XS19") (pin "43") (pintype "passive")))
    (net (code "744") (name "/D15_A_11") (class "Default") (node (ref "XS21") (pin "43") (pintype "passive")))
    (net (code "745") (name "/D15_A_12") (class "Default") (node (ref "XS23") (pin "43") (pintype "passive")))
    (net (code "746") (name "/D15_B_1") (class "Default") (node (ref "XS1") (pin "12") (pintype "passive")))
    (net (code "747") (name "/D15_B_2") (class "Default") (node (ref "XS3") (pin "12") (pintype "passive")))
    (net (code "748") (name "/D15_B_3") (class "Default") (node (ref "XS5") (pin "12") (pintype "passive")))
    (net (code "749") (name "/D15_B_4") (class "Default") (node (ref "XS7") (pin "12") (pintype "passive")))
    (net (code "750") (name "/D15_B_5") (class "Default") (node (ref "XS9") (pin "12") (pintype "passive")))
    (net (code "751") (name "/D15_B_6") (class "Default") (node (ref "XS11") (pin "12") (pintype "passive")))
    (net (code "752") (name "/D15_B_7") (class "Default") (node (ref "XS13") (pin "12") (pintype "passive")))
    (net (code "753") (name "/D15_B_8") (class "Default") (node (ref "XS15") (pin "12") (pintype "passive")))
    (net (code "754") (name "/D15_B_9") (class "Default") (node (ref "XS17") (pin "12") (pintype "passive")))
    (net (code "755") (name "/D15_B_10") (class "Default") (node (ref "XS19") (pin "12") (pintype "passive")))
    (net (code "756") (name "/D15_B_11") (class "Default") (node (ref "XS21") (pin "12") (pintype "passive")))
    (net (code "757") (name "/D15_B_12") (class "Default") (node (ref "XS23") (pin "12") (pintype "passive")))
    (net (code "758") (name "/D15_C_1") (class "Default") (node (ref "XS2") (pin "46") (pintype "passive")))
    (net (code "759") (name "/D15_C_2") (class "Default") (node (ref "XS4") (pin "46") (pintype "passive")))
    (net (code "760") (name "/D15_C_3") (class "Default") (node (ref "XS6") (pin "46") (pintype "passive")))
    (net (code "761") (name "/D15_C_4") (class "Default") (node (ref "XS8") (pin "46") (pintype "passive")))
    (net (code "762") (name "/D15_C_5") (class "Default") (node (ref "XS10") (pin "46") (pintype "passive")))
    (net (code "763") (name "/D15_C_6") (class "Default") (node (ref "XS12") (pin "46") (pintype "passive")))
    (net (code "764") (name "/D15_C_7") (class "Default") (node (ref "XS14") (pin "46") (pintype "passive")))
    (net (code "765") (name "/D15_C_8") (class "Default") (node (ref "XS16") (pin "46") (pintype "passive")))
    (net (code "766") (name "/D15_C_9") (class "Default") (node (ref "XS18") (pin "46") (pintype "passive")))
    (net (code "767") (name "/D15_C_10") (class "Default") (node (ref "XS20") (pin "46") (pintype "passive")))
    (net (code "768") (name "/D15_C_11") (class "Default") (node (ref "XS22") (pin "46") (pintype "passive")))
    (net (code "769") (name "/D15_C_12") (class "Default") (node (ref "XS24") (pin "46") (pintype "passive")))
    (net (code "770") (name "/D15_D_1") (class "Default") (node (ref "XS2") (pin "2") (pintype "passive")))
    (net (code "771") (name "/D15_D_2") (class "Default") (node (ref "XS4") (pin "2") (pintype "passive")))
    (net (code "772") (name "/D15_D_3") (class "Default") (node (ref "XS6") (pin "2") (pintype "passive")))
    (net (code "773") (name "/D15_D_4") (class "Default") (node (ref "XS8") (pin "2") (pintype "passive")))
    (net (code "774") (name "/D15_D_5") (class "Default") (node (ref "XS10") (pin "2") (pintype "passive")))
    (net (code "775") (name "/D15_D_6") (class "Default") (node (ref "XS12") (pin "2") (pintype "passive")))
    (net (code "776") (name "/D15_D_7") (class "Default") (node (ref "XS14") (pin "2") (pintype "passive")))
    (net (code "777") (name "/D15_D_8") (class "Default") (node (ref "XS16") (pin "2") (pintype "passive")))
    (net (code "778") (name "/D15_D_9") (class "Default") (node (ref "XS18") (pin "2") (pintype "passive")))
    (net (code "779") (name "/D15_D_10") (class "Default") (node (ref "XS20") (pin "2") (pintype "passive")))
    (net (code "780") (name "/D15_D_11") (class "Default") (node (ref "XS22") (pin "2") (pintype "passive")))
    (net (code "781") (name "/D15_D_12") (class "Default") (node (ref "XS24") (pin "2") (pintype "passive")))
    (net (code "782") (name "/D16_A_1") (class "Default") (node (ref "XS1") (pin "19") (pintype "passive")))
    (net (code "783") (name "/D16_A_2") (class "Default") (node (ref "XS3") (pin "19") (pintype "passive")))
    (net (code "784") (name "/D16_A_3") (class "Default") (node (ref "XS5") (pin "19") (pintype "passive")))
    (net (code "785") (name "/D16_A_4") (class "Default") (node (ref "XS7") (pin "19") (pintype "passive")))
    (net (code "786") (name "/D16_A_5") (class "Default") (node (ref "XS9") (pin "19") (pintype "passive")))
    (net (code "787") (name "/D16_A_6") (class "Default") (node (ref "XS11") (pin "19") (pintype "passive")))
    (net (code "788") (name "/D16_A_7") (class "Default") (node (ref "XS13") (pin "19") (pintype "passive")))
    (net (code "789") (name "/D16_A_8") (class "Default") (node (ref "XS15") (pin "19") (pintype "passive")))
    (net (code "790") (name "/D16_A_9") (class "Default") (node (ref "XS17") (pin "19") (pintype "passive")))
    (net (code "791") (name "/D16_A_10") (class "Default") (node (ref "XS19") (pin "19") (pintype "passive")))
    (net (code "792") (name "/D16_A_11") (class "Default") (node (ref "XS21") (pin "19") (pintype "passive")))
    (net (code "793") (name "/D16_A_12") (class "Default") (node (ref "XS23") (pin "19") (pintype "passive")))
    (net (code "794") (name "/D16_B_1") (class "Default") (node (ref "XS1") (pin "50") (pintype "passive")))
    (net (code "795") (name "/D16_B_2") (class "Default") (node (ref "XS3") (pin "50") (pintype "passive")))
    (net (code "796") (name "/D16_B_3") (class "Default") (node (ref "XS5") (pin "50") (pintype "passive")))
    (net (code "797") (name "/D16_B_4") (class "Default") (node (ref "XS7") (pin "50") (pintype "passive")))
    (net (code "798") (name "/D16_B_5") (class "Default") (node (ref "XS9") (pin "50") (pintype "passive")))
    (net (code "799") (name "/D16_B_6") (class "Default") (node (ref "XS11") (pin "50") (pintype "passive")))
    (net (code "800") (name "/D16_B_7") (class "Default") (node (ref "XS13") (pin "50") (pintype "passive")))
    (net (code "801") (name "/D16_B_8") (class "Default") (node (ref "XS15") (pin "50") (pintype "passive")))
    (net (code "802") (name "/D16_B_9") (class "Default") (node (ref "XS17") (pin "50") (pintype "passive")))
    (net (code "803") (name "/D16_B_10") (class "Default") (node (ref "XS19") (pin "50") (pintype "passive")))
    (net (code "804") (name "/D16_B_11") (class "Default") (node (ref "XS21") (pin "50") (pintype "passive")))
    (net (code "805") (name "/D16_B_12") (class "Default") (node (ref "XS23") (pin "50") (pintype "passive")))
    (net (code "806") (name "/D16_C_1") (class "Default") (node (ref "XS2") (pin "20") (pintype "passive")))
    (net (code "807") (name "/D16_C_2") (class "Default") (node (ref "XS4") (pin "20") (pintype "passive")))
    (net (code "808") (name "/D16_C_3") (class "Default") (node (ref "XS6") (pin "20") (pintype "passive")))
    (net (code "809") (name "/D16_C_4") (class "Default") (node (ref "XS8") (pin "20") (pintype "passive")))
    (net (code "810") (name "/D16_C_5") (class "Default") (node (ref "XS10") (pin "20") (pintype "passive")))
    (net (code "811") (name "/D16_C_6") (class "Default") (node (ref "XS12") (pin "20") (pintype "passive")))
    (net (code "812") (name "/D16_C_7") (class "Default") (node (ref "XS14") (pin "20") (pintype "passive")))
    (net (code "813") (name "/D16_C_8") (class "Default") (node (ref "XS16") (pin "20") (pintype "passive")))
    (net (code "814") (name "/D16_C_9") (class "Default") (node (ref "XS18") (pin "20") (pintype "passive")))
    (net (code "815") (name "/D16_C_10") (class "Default") (node (ref "XS20") (pin "20") (pintype "passive")))
    (net (code "816") (name "/D16_C_11") (class "Default") (node (ref "XS22") (pin "20") (pintype "passive")))
    (net (code "817") (name "/D16_C_12") (class "Default") (node (ref "XS24") (pin "20") (pintype "passive")))
    (net (code "818") (name "/D16_D_1") (class "Default") (node (ref "XS2") (pin "39") (pintype "passive")))
    (net (code "819") (name "/D16_D_2") (class "Default") (node (ref "XS4") (pin "39") (pintype "passive")))
    (net (code "820") (name "/D16_D_3") (class "Default") (node (ref "XS6") (pin "39") (pintype "passive")))
    (net (code "821") (name "/D16_D_4") (class "Default") (node (ref "XS8") (pin "39") (pintype "passive")))
    (net (code "822") (name "/D16_D_5") (class "Default") (node (ref "XS10") (pin "39") (pintype "passive")))
    (net (code "823") (name "/D16_D_6") (class "Default") (node (ref "XS12") (pin "39") (pintype "passive")))
    (net (code "824") (name "/D16_D_7") (class "Default") (node (ref "XS14") (pin "39") (pintype "passive")))
    (net (code "825") (name "/D16_D_8") (class "Default") (node (ref "XS16") (pin "39") (pintype "passive")))
    (net (code "826") (name "/D16_D_9") (class "Default") (node (ref "XS18") (pin "39") (pintype "passive")))
    (net (code "827") (name "/D16_D_10") (class "Default") (node (ref "XS20") (pin "39") (pintype "passive")))
    (net (code "828") (name "/D16_D_11") (class "Default") (node (ref "XS22") (pin "39") (pintype "passive")))
    (net (code "829") (name "/D16_D_12") (class "Default") (node (ref "XS24") (pin "39") (pintype "passive")))
    (net (code "830") (name "/GNDD") (class "Default")
      (node (ref "XS1") (pin "25") (pintype "passive"))
      (node (ref "XS1") (pin "31") (pintype "passive"))
      (node (ref "XS1") (pin "35") (pintype "passive"))
      (node (ref "XS1") (pin "39") (pintype "passive"))
      (node (ref "XS1") (pin "4") (pintype "passive"))
      (node (ref "XS1") (pin "8") (pintype "passive"))
      (node (ref "XS10") (pin "10") (pintype "passive"))
      (node (ref "XS10") (pin "14") (pintype "passive"))
      (node (ref "XS10") (pin "29") (pintype "passive"))
      (node (ref "XS11") (pin "25") (pintype "passive"))
      (node (ref "XS11") (pin "31") (pintype "passive"))
      (node (ref "XS11") (pin "35") (pintype "passive"))
      (node (ref "XS11") (pin "39") (pintype "passive"))
      (node (ref "XS11") (pin "4") (pintype "passive"))
      (node (ref "XS11") (pin "8") (pintype "passive"))
      (node (ref "XS12") (pin "10") (pintype "passive"))
      (node (ref "XS12") (pin "14") (pintype "passive"))
      (node (ref "XS12") (pin "29") (pintype "passive"))
      (node (ref "XS13") (pin "25") (pintype "passive"))
      (node (ref "XS13") (pin "31") (pintype "passive"))
      (node (ref "XS13") (pin "35") (pintype "passive"))
      (node (ref "XS13") (pin "39") (pintype "passive"))
      (node (ref "XS13") (pin "4") (pintype "passive"))
      (node (ref "XS13") (pin "8") (pintype "passive"))
      (node (ref "XS14") (pin "10") (pintype "passive"))
      (node (ref "XS14") (pin "14") (pintype "passive"))
      (node (ref "XS14") (pin "29") (pintype "passive"))
      (node (ref "XS15") (pin "25") (pintype "passive"))
      (node (ref "XS15") (pin "31") (pintype "passive"))
      (node (ref "XS15") (pin "35") (pintype "passive"))
      (node (ref "XS15") (pin "39") (pintype "passive"))
      (node (ref "XS15") (pin "4") (pintype "passive"))
      (node (ref "XS15") (pin "8") (pintype "passive"))
      (node (ref "XS16") (pin "10") (pintype "passive"))
      (node (ref "XS16") (pin "14") (pintype "passive"))
      (node (ref "XS16") (pin "29") (pintype "passive"))
      (node (ref "XS17") (pin "25") (pintype "passive"))
      (node (ref "XS17") (pin "31") (pintype "passive"))
      (node (ref "XS17") (pin "35") (pintype "passive"))
      (node (ref "XS17") (pin "39") (pintype "passive"))
      (node (ref "XS17") (pin "4") (pintype "passive"))
      (node (ref "XS17") (pin "8") (pintype "passive"))
      (node (ref "XS18") (pin "10") (pintype "passive"))
      (node (ref "XS18") (pin "14") (pintype "passive"))
      (node (ref "XS18") (pin "29") (pintype "passive"))
      (node (ref "XS19") (pin "25") (pintype "passive"))
      (node (ref "XS19") (pin "31") (pintype "passive"))
      (node (ref "XS19") (pin "35") (pintype "passive"))
      (node (ref "XS19") (pin "39") (pintype "passive"))
      (node (ref "XS19") (pin "4") (pintype "passive"))
      (node (ref "XS19") (pin "8") (pintype "passive"))
      (node (ref "XS2") (pin "10") (pintype "passive"))
      (node (ref "XS2") (pin "14") (pintype "passive"))
      (node (ref "XS2") (pin "29") (pintype "passive"))
      (node (ref "XS20") (pin "10") (pintype "passive"))
      (node (ref "XS20") (pin "14") (pintype "passive"))
      (node (ref "XS20") (pin "29") (pintype "passive"))
      (node (ref "XS21") (pin "25") (pintype "passive"))
      (node (ref "XS21") (pin "31") (pintype "passive"))
      (node (ref "XS21") (pin "35") (pintype "passive"))
      (node (ref "XS21") (pin "39") (pintype "passive"))
      (node (ref "XS21") (pin "4") (pintype "passive"))
      (node (ref "XS21") (pin "8") (pintype "passive"))
      (node (ref "XS22") (pin "10") (pintype "passive"))
      (node (ref "XS22") (pin "14") (pintype "passive"))
      (node (ref "XS22") (pin "29") (pintype "passive"))
      (node (ref "XS23") (pin "25") (pintype "passive"))
      (node (ref "XS23") (pin "31") (pintype "passive"))
      (node (ref "XS23") (pin "35") (pintype "passive"))
      (node (ref "XS23") (pin "39") (pintype "passive"))
      (node (ref "XS23") (pin "4") (pintype "passive"))
      (node (ref "XS23") (pin "8") (pintype "passive"))
      (node (ref "XS24") (pin "10") (pintype "passive"))
      (node (ref "XS24") (pin "14") (pintype "passive"))
      (node (ref "XS24") (pin "29") (pintype "passive"))
      (node (ref "XS3") (pin "25") (pintype "passive"))
      (node (ref "XS3") (pin "31") (pintype "passive"))
      (node (ref "XS3") (pin "35") (pintype "passive"))
      (node (ref "XS3") (pin "39") (pintype "passive"))
      (node (ref "XS3") (pin "4") (pintype "passive"))
      (node (ref "XS3") (pin "8") (pintype "passive"))
      (node (ref "XS4") (pin "10") (pintype "passive"))
      (node (ref "XS4") (pin "14") (pintype "passive"))
      (node (ref "XS4") (pin "29") (pintype "passive"))
      (node (ref "XS5") (pin "25") (pintype "passive"))
      (node (ref "XS5") (pin "31") (pintype "passive"))
      (node (ref "XS5") (pin "35") (pintype "passive"))
      (node (ref "XS5") (pin "39") (pintype "passive"))
      (node (ref "XS5") (pin "4") (pintype "passive"))
      (node (ref "XS5") (pin "8") (pintype "passive"))
      (node (ref "XS6") (pin "10") (pintype "passive"))
      (node (ref "XS6") (pin "14") (pintype "passive"))
      (node (ref "XS6") (pin "29") (pintype "passive"))
      (node (ref "XS7") (pin "25") (pintype "passive"))
      (node (ref "XS7") (pin "31") (pintype "passive"))
      (node (ref "XS7") (pin "35") (pintype "passive"))
      (node (ref "XS7") (pin "39") (pintype "passive"))
      (node (ref "XS7") (pin "4") (pintype "passive"))
      (node (ref "XS7") (pin "8") (pintype "passive"))
      (node (ref "XS8") (pin "10") (pintype "passive"))
      (node (ref "XS8") (pin "14") (pintype "passive"))
      (node (ref "XS8") (pin "29") (pintype "passive"))
      (node (ref "XS9") (pin "25") (pintype "passive"))
      (node (ref "XS9") (pin "31") (pintype "passive"))
      (node (ref "XS9") (pin "35") (pintype "passive"))
      (node (ref "XS9") (pin "39") (pintype "passive"))
      (node (ref "XS9") (pin "4") (pintype "passive"))
      (node (ref "XS9") (pin "8") (pintype "passive"))
    )
    (net (code "831") (name "/LD_A_1") (class "Default") (node (ref "XS1") (pin "28") (pintype "passive")))
    (net (code "832") (name "/LD_A_2") (class "Default") (node (ref "XS3") (pin "28") (pintype "passive")))
    (net (code "833") (name "/LD_A_3") (class "Default") (node (ref "XS5") (pin "28") (pintype "passive")))
    (net (code "834") (name "/LD_A_4") (class "Default") (node (ref "XS7") (pin "28") (pintype "passive")))
    (net (code "835") (name "/LD_A_5") (class "Default") (node (ref "XS9") (pin "28") (pintype "passive")))
    (net (code "836") (name "/LD_A_6") (class "Default") (node (ref "XS11") (pin "28") (pintype "passive")))
    (net (code "837") (name "/LD_A_7") (class "Default") (node (ref "XS13") (pin "28") (pintype "passive")))
    (net (code "838") (name "/LD_A_8") (class "Default") (node (ref "XS15") (pin "28") (pintype "passive")))
    (net (code "839") (name "/LD_A_9") (class "Default") (node (ref "XS17") (pin "28") (pintype "passive")))
    (net (code "840") (name "/LD_A_10") (class "Default") (node (ref "XS19") (pin "28") (pintype "passive")))
    (net (code "841") (name "/LD_A_11") (class "Default") (node (ref "XS21") (pin "28") (pintype "passive")))
    (net (code "842") (name "/LD_A_12") (class "Default") (node (ref "XS23") (pin "28") (pintype "passive")))
    (net (code "843") (name "/LD_B_1") (class "Default") (node (ref "XS1") (pin "22") (pintype "passive")))
    (net (code "844") (name "/LD_B_2") (class "Default") (node (ref "XS3") (pin "22") (pintype "passive")))
    (net (code "845") (name "/LD_B_3") (class "Default") (node (ref "XS5") (pin "22") (pintype "passive")))
    (net (code "846") (name "/LD_B_4") (class "Default") (node (ref "XS7") (pin "22") (pintype "passive")))
    (net (code "847") (name "/LD_B_5") (class "Default") (node (ref "XS9") (pin "22") (pintype "passive")))
    (net (code "848") (name "/LD_B_6") (class "Default") (node (ref "XS11") (pin "22") (pintype "passive")))
    (net (code "849") (name "/LD_B_7") (class "Default") (node (ref "XS13") (pin "22") (pintype "passive")))
    (net (code "850") (name "/LD_B_8") (class "Default") (node (ref "XS15") (pin "22") (pintype "passive")))
    (net (code "851") (name "/LD_B_9") (class "Default") (node (ref "XS17") (pin "22") (pintype "passive")))
    (net (code "852") (name "/LD_B_10") (class "Default") (node (ref "XS19") (pin "22") (pintype "passive")))
    (net (code "853") (name "/LD_B_11") (class "Default") (node (ref "XS21") (pin "22") (pintype "passive")))
    (net (code "854") (name "/LD_B_12") (class "Default") (node (ref "XS23") (pin "22") (pintype "passive")))
    (net (code "855") (name "/LD_C_1") (class "Default") (node (ref "XS2") (pin "36") (pintype "passive")))
    (net (code "856") (name "/LD_C_2") (class "Default") (node (ref "XS4") (pin "36") (pintype "passive")))
    (net (code "857") (name "/LD_C_3") (class "Default") (node (ref "XS6") (pin "36") (pintype "passive")))
    (net (code "858") (name "/LD_C_4") (class "Default") (node (ref "XS8") (pin "36") (pintype "passive")))
    (net (code "859") (name "/LD_C_5") (class "Default") (node (ref "XS10") (pin "36") (pintype "passive")))
    (net (code "860") (name "/LD_C_6") (class "Default") (node (ref "XS12") (pin "36") (pintype "passive")))
    (net (code "861") (name "/LD_C_7") (class "Default") (node (ref "XS14") (pin "36") (pintype "passive")))
    (net (code "862") (name "/LD_C_8") (class "Default") (node (ref "XS16") (pin "36") (pintype "passive")))
    (net (code "863") (name "/LD_C_9") (class "Default") (node (ref "XS18") (pin "36") (pintype "passive")))
    (net (code "864") (name "/LD_C_10") (class "Default") (node (ref "XS20") (pin "36") (pintype "passive")))
    (net (code "865") (name "/LD_C_11") (class "Default") (node (ref "XS22") (pin "36") (pintype "passive")))
    (net (code "866") (name "/LD_C_12") (class "Default") (node (ref "XS24") (pin "36") (pintype "passive")))
    (net (code "867") (name "/LD_D_1") (class "Default") (node (ref "XS2") (pin "17") (pintype "passive")))
    (net (code "868") (name "/LD_D_2") (class "Default") (node (ref "XS4") (pin "17") (pintype "passive")))
    (net (code "869") (name "/LD_D_3") (class "Default") (node (ref "XS6") (pin "17") (pintype "passive")))
    (net (code "870") (name "/LD_D_4") (class "Default") (node (ref "XS8") (pin "17") (pintype "passive")))
    (net (code "871") (name "/LD_D_5") (class "Default") (node (ref "XS10") (pin "17") (pintype "passive")))
    (net (code "872") (name "/LD_D_6") (class "Default") (node (ref "XS12") (pin "17") (pintype "passive")))
    (net (code "873") (name "/LD_D_7") (class "Default") (node (ref "XS14") (pin "17") (pintype "passive")))
    (net (code "874") (name "/LD_D_8") (class "Default") (node (ref "XS16") (pin "17") (pintype "passive")))
    (net (code "875") (name "/LD_D_9") (class "Default") (node (ref "XS18") (pin "17") (pintype "passive")))
    (net (code "876") (name "/LD_D_10") (class "Default") (node (ref "XS20") (pin "17") (pintype "passive")))
    (net (code "877") (name "/LD_D_11") (class "Default") (node (ref "XS22") (pin "17") (pintype "passive")))
    (net (code "878") (name "/LD_D_12") (class "Default") (node (ref "XS24") (pin "17") (pintype "passive")))
    (net (code "879") (name "/SUBA1_DLY_5V0") (class "Default")
      (node (ref "XS2") (pin "50") (pintype "passive"))
    )
    (net (code "880") (name "/SUBA1_DLY_5V1") (class "Default")
      (node (ref "XS2") (pin "33") (pintype "passive"))
    )
    (net (code "881") (name "/SUBA1_DLY_5V2") (class "Default")
      (node (ref "XS2") (pin "6") (pintype "passive"))
    )
    (net (code "882") (name "/SUBA2_DLY_5V0") (class "Default")
      (node (ref "XS4") (pin "50") (pintype "passive"))
    )
    (net (code "883") (name "/SUBA2_DLY_5V1") (class "Default")
      (node (ref "XS4") (pin "33") (pintype "passive"))
    )
    (net (code "884") (name "/SUBA2_DLY_5V2") (class "Default")
      (node (ref "XS4") (pin "6") (pintype "passive"))
    )
    (net (code "885") (name "/SUBA3_DLY_5V0") (class "Default")
      (node (ref "XS6") (pin "50") (pintype "passive"))
    )
    (net (code "886") (name "/SUBA3_DLY_5V1") (class "Default")
      (node (ref "XS6") (pin "33") (pintype "passive"))
    )
    (net (code "887") (name "/SUBA3_DLY_5V2") (class "Default")
      (node (ref "XS6") (pin "6") (pintype "passive"))
    )
    (net (code "888") (name "/SUBA4_DLY_5V0") (class "Default")
      (node (ref "XS8") (pin "50") (pintype "passive"))
    )
    (net (code "889") (name "/SUBA4_DLY_5V1") (class "Default")
      (node (ref "XS8") (pin "33") (pintype "passive"))
    )
    (net (code "890") (name "/SUBA4_DLY_5V2") (class "Default")
      (node (ref "XS8") (pin "6") (pintype "passive"))
    )
    (net (code "891") (name "/SUBA5_DLY_5V0") (class "Default")
      (node (ref "XS10") (pin "50") (pintype "passive"))
    )
    (net (code "892") (name "/SUBA5_DLY_5V1") (class "Default")
      (node (ref "XS10") (pin "33") (pintype "passive"))
    )
    (net (code "893") (name "/SUBA5_DLY_5V2") (class "Default")
      (node (ref "XS10") (pin "6") (pintype "passive"))
    )
    (net (code "894") (name "/SUBA6_DLY_5V0") (class "Default")
      (node (ref "XS12") (pin "50") (pintype "passive"))
    )
    (net (code "895") (name "/SUBA6_DLY_5V1") (class "Default")
      (node (ref "XS12") (pin "33") (pintype "passive"))
    )
    (net (code "896") (name "/SUBA6_DLY_5V2") (class "Default")
      (node (ref "XS12") (pin "6") (pintype "passive"))
    )
    (net (code "897") (name "/SUBA7_DLY_5V0") (class "Default")
      (node (ref "XS14") (pin "50") (pintype "passive"))
    )
    (net (code "898") (name "/SUBA7_DLY_5V1") (class "Default")
      (node (ref "XS14") (pin "33") (pintype "passive"))
    )
    (net (code "899") (name "/SUBA7_DLY_5V2") (class "Default")
      (node (ref "XS14") (pin "6") (pintype "passive"))
    )
    (net (code "900") (name "/SUBA8_DLY_5V0") (class "Default")
      (node (ref "XS16") (pin "50") (pintype "passive"))
    )
    (net (code "901") (name "/SUBA8_DLY_5V1") (class "Default")
      (node (ref "XS16") (pin "33") (pintype "passive"))
    )
    (net (code "902") (name "/SUBA8_DLY_5V2") (class "Default")
      (node (ref "XS16") (pin "6") (pintype "passive"))
    )
    (net (code "903") (name "/SUBA9_DLY_5V0") (class "Default")
      (node (ref "XS18") (pin "50") (pintype "passive"))
    )
    (net (code "904") (name "/SUBA9_DLY_5V1") (class "Default")
      (node (ref "XS18") (pin "33") (pintype "passive"))
    )
    (net (code "905") (name "/SUBA9_DLY_5V2") (class "Default")
      (node (ref "XS18") (pin "6") (pintype "passive"))
    )
    (net (code "906") (name "/SUBA10_DLY_5V0") (class "Default")
      (node (ref "XS20") (pin "50") (pintype "passive"))
    )
    (net (code "907") (name "/SUBA10_DLY_5V1") (class "Default")
      (node (ref "XS20") (pin "33") (pintype "passive"))
    )
    (net (code "908") (name "/SUBA10_DLY_5V2") (class "Default")
      (node (ref "XS20") (pin "6") (pintype "passive"))
    )
    (net (code "909") (name "/SUBA11_DLY_5V0") (class "Default")
      (node (ref "XS22") (pin "50") (pintype "passive"))
    )
    (net (code "910") (name "/SUBA11_DLY_5V1") (class "Default")
      (node (ref "XS22") (pin "33") (pintype "passive"))
    )
    (net (code "911") (name "/SUBA11_DLY_5V2") (class "Default")
      (node (ref "XS22") (pin "6") (pintype "passive"))
    )
    (net (code "912") (name "/SUBA12_DLY_5V0") (class "Default")
      (node (ref "XS24") (pin "50") (pintype "passive"))
    )
    (net (code "913") (name "/SUBA12_DLY_5V1") (class "Default")
      (node (ref "XS24") (pin "33") (pintype "passive"))
    )
    (net (code "914") (name "/SUBA12_DLY_5V2") (class "Default")
      (node (ref "XS24") (pin "6") (pintype "passive"))
    )
  )
)
